# GD32F470IIH6.net
KiCad netlist of a schematic drawn in EasyEDA Pro
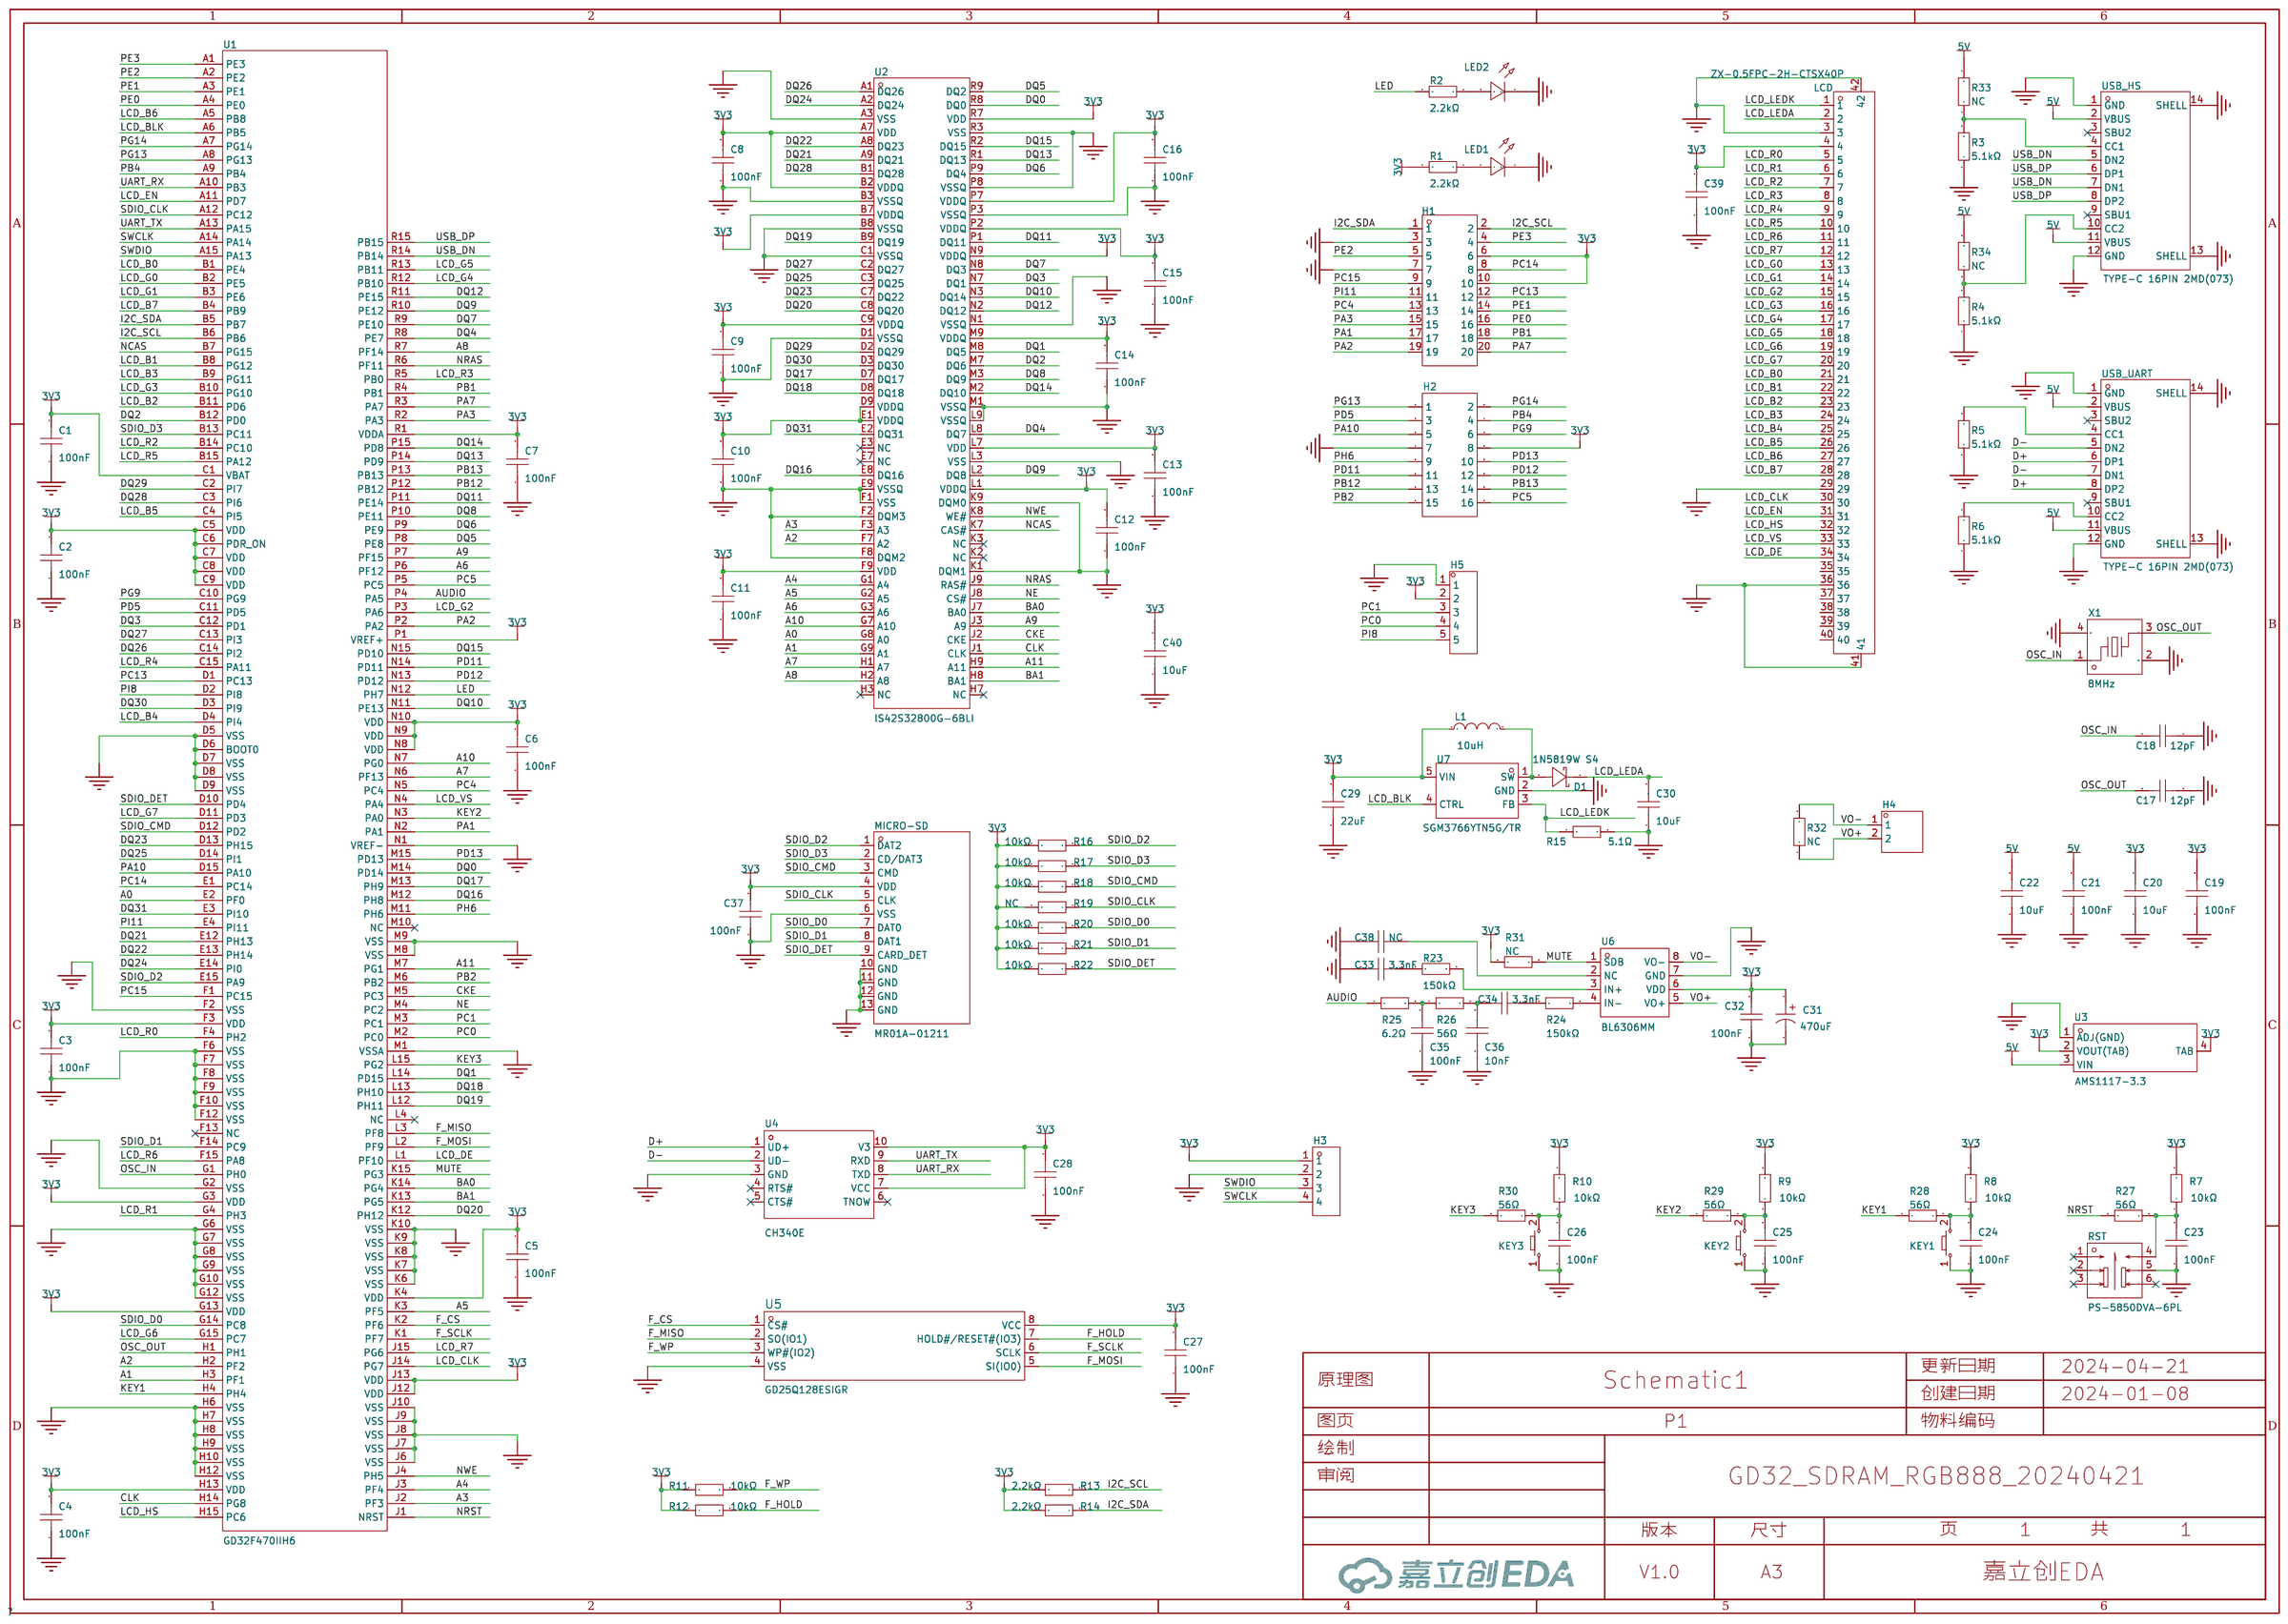
[diagram p0: schematic sheet]

(export (version "E")
  (design (tool "Eeschema 10.0.6"))
  (components
    (comp (ref "C1")
      (value "100nF")
      (footprint "easyedapro:C0402")
      (description "容值:100nF;精度:±10%;额定电压:16V;材质(温度系数):X7R;")
      (fields
        (field (name "Manufacturer Part") "CC0402KRX7R7BB104")
        (field (name "Manufacturer") "YAGEO(国巨)")
      )
      (libsource (lib "easyedapro") (part "CapAcitance"))
    )
    (comp (ref "C2")
      (value "100nF")
      (footprint "easyedapro:C0402")
      (description "容值:100nF;精度:±10%;额定电压:16V;材质(温度系数):X7R;")
      (fields
        (field (name "Manufacturer Part") "CC0402KRX7R7BB104")
        (field (name "Manufacturer") "YAGEO(国巨)")
      )
      (libsource (lib "easyedapro") (part "CapAcitance"))
    )
    (comp (ref "C3")
      (value "100nF")
      (footprint "easyedapro:C0402")
      (description "容值:100nF;精度:±10%;额定电压:16V;材质(温度系数):X7R;")
      (fields
        (field (name "Manufacturer Part") "CC0402KRX7R7BB104")
        (field (name "Manufacturer") "YAGEO(国巨)")
      )
      (libsource (lib "easyedapro") (part "CapAcitance"))
    )
    (comp (ref "C4")
      (value "100nF")
      (footprint "easyedapro:C0402")
      (description "容值:100nF;精度:±10%;额定电压:16V;材质(温度系数):X7R;")
      (fields
        (field (name "Manufacturer Part") "CC0402KRX7R7BB104")
        (field (name "Manufacturer") "YAGEO(国巨)")
      )
      (libsource (lib "easyedapro") (part "CapAcitance"))
    )
    (comp (ref "C5")
      (value "100nF")
      (footprint "easyedapro:C0402")
      (description "容值:100nF;精度:±10%;额定电压:16V;材质(温度系数):X7R;")
      (fields
        (field (name "Manufacturer Part") "CC0402KRX7R7BB104")
        (field (name "Manufacturer") "YAGEO(国巨)")
      )
      (libsource (lib "easyedapro") (part "CapAcitance"))
    )
    (comp (ref "C6")
      (value "100nF")
      (footprint "easyedapro:C0402")
      (description "容值:100nF;精度:±10%;额定电压:16V;材质(温度系数):X7R;")
      (fields
        (field (name "Manufacturer Part") "CC0402KRX7R7BB104")
        (field (name "Manufacturer") "YAGEO(国巨)")
      )
      (libsource (lib "easyedapro") (part "CapAcitance"))
    )
    (comp (ref "C7")
      (value "100nF")
      (footprint "easyedapro:C0402")
      (description "容值:100nF;精度:±10%;额定电压:16V;材质(温度系数):X7R;")
      (fields
        (field (name "Manufacturer Part") "CC0402KRX7R7BB104")
        (field (name "Manufacturer") "YAGEO(国巨)")
      )
      (libsource (lib "easyedapro") (part "CapAcitance"))
    )
    (comp (ref "C8")
      (value "100nF")
      (footprint "easyedapro:C0402")
      (description "容值:100nF;精度:±10%;额定电压:16V;材质(温度系数):X7R;")
      (fields
        (field (name "Manufacturer Part") "CC0402KRX7R7BB104")
        (field (name "Manufacturer") "YAGEO(国巨)")
      )
      (libsource (lib "easyedapro") (part "CapAcitance"))
    )
    (comp (ref "C9")
      (value "100nF")
      (footprint "easyedapro:C0402")
      (description "容值:100nF;精度:±10%;额定电压:16V;材质(温度系数):X7R;")
      (fields
        (field (name "Manufacturer Part") "CC0402KRX7R7BB104")
        (field (name "Manufacturer") "YAGEO(国巨)")
      )
      (libsource (lib "easyedapro") (part "CapAcitance"))
    )
    (comp (ref "C10")
      (value "100nF")
      (footprint "easyedapro:C0402")
      (description "容值:100nF;精度:±10%;额定电压:16V;材质(温度系数):X7R;")
      (fields
        (field (name "Manufacturer Part") "CC0402KRX7R7BB104")
        (field (name "Manufacturer") "YAGEO(国巨)")
      )
      (libsource (lib "easyedapro") (part "CapAcitance"))
    )
    (comp (ref "C11")
      (value "100nF")
      (footprint "easyedapro:C0402")
      (description "容值:100nF;精度:±10%;额定电压:16V;材质(温度系数):X7R;")
      (fields
        (field (name "Manufacturer Part") "CC0402KRX7R7BB104")
        (field (name "Manufacturer") "YAGEO(国巨)")
      )
      (libsource (lib "easyedapro") (part "CapAcitance"))
    )
    (comp (ref "C12")
      (value "100nF")
      (footprint "easyedapro:C0402")
      (description "容值:100nF;精度:±10%;额定电压:16V;材质(温度系数):X7R;")
      (fields
        (field (name "Manufacturer Part") "CC0402KRX7R7BB104")
        (field (name "Manufacturer") "YAGEO(国巨)")
      )
      (libsource (lib "easyedapro") (part "CapAcitance"))
    )
    (comp (ref "C13")
      (value "100nF")
      (footprint "easyedapro:C0402")
      (description "容值:100nF;精度:±10%;额定电压:16V;材质(温度系数):X7R;")
      (fields
        (field (name "Manufacturer Part") "CC0402KRX7R7BB104")
        (field (name "Manufacturer") "YAGEO(国巨)")
      )
      (libsource (lib "easyedapro") (part "CapAcitance"))
    )
    (comp (ref "C14")
      (value "100nF")
      (footprint "easyedapro:C0402")
      (description "容值:100nF;精度:±10%;额定电压:16V;材质(温度系数):X7R;")
      (fields
        (field (name "Manufacturer Part") "CC0402KRX7R7BB104")
        (field (name "Manufacturer") "YAGEO(国巨)")
      )
      (libsource (lib "easyedapro") (part "CapAcitance"))
    )
    (comp (ref "C15")
      (value "100nF")
      (footprint "easyedapro:C0402")
      (description "容值:100nF;精度:±10%;额定电压:16V;材质(温度系数):X7R;")
      (fields
        (field (name "Manufacturer Part") "CC0402KRX7R7BB104")
        (field (name "Manufacturer") "YAGEO(国巨)")
      )
      (libsource (lib "easyedapro") (part "CapAcitance"))
    )
    (comp (ref "C16")
      (value "100nF")
      (footprint "easyedapro:C0402")
      (description "容值:100nF;精度:±10%;额定电压:16V;材质(温度系数):X7R;")
      (fields
        (field (name "Manufacturer Part") "CC0402KRX7R7BB104")
        (field (name "Manufacturer") "YAGEO(国巨)")
      )
      (libsource (lib "easyedapro") (part "CapAcitance"))
    )
    (comp (ref "C17")
      (value "12pF")
      (footprint "easyedapro:C0603")
      (fields
        (field (name "Manufacturer Part") "CL10C120JB8NNNC")
        (field (name "Manufacturer") "SAMSUNG(三星)")
        (field (name "Tolerance") "±5%")
      )
      (libsource (lib "easyedapro") (part "CapAcitance"))
    )
    (comp (ref "C18")
      (value "12pF")
      (footprint "easyedapro:C0603")
      (fields
        (field (name "Manufacturer Part") "CL10C120JB8NNNC")
        (field (name "Manufacturer") "SAMSUNG(三星)")
        (field (name "Tolerance") "±5%")
      )
      (libsource (lib "easyedapro") (part "CapAcitance"))
    )
    (comp (ref "C19")
      (value "100nF")
      (footprint "easyedapro:C0805")
      (description "容值:100nF;精度:±10%;额定电压:50V;材质(温度系数):X7R;")
      (fields (field (name "Manufacturer Part") "0603B104K500NT") (field (name "Manufacturer") "FH(风华)"))
      (libsource (lib "easyedapro") (part "CapAcitance"))
    )
    (comp (ref "C20")
      (value "10uF")
      (footprint "easyedapro:C0805")
      (description "容值:10uF;精度:±10%;额定电压:25V;材质(温度系数):X5R;")
      (fields
        (field (name "Manufacturer Part") "CL21A106KAYNNNE")
        (field (name "Manufacturer") "SAMSUNG(三星)")
      )
      (libsource (lib "easyedapro") (part "CapAcitance"))
    )
    (comp (ref "C21")
      (value "100nF")
      (footprint "easyedapro:C0805")
      (fields
        (field (name "Manufacturer Part") "0603B104K500NT")
        (field (name "Manufacturer") "FH(风华)")
        (field (name "Tolerance") "±10%")
      )
      (libsource (lib "easyedapro") (part "CapAcitance"))
    )
    (comp (ref "C22")
      (value "10uF")
      (footprint "easyedapro:C0805")
      (description "容值:10uF;精度:±10%;额定电压:25V;材质(温度系数):X5R;")
      (fields
        (field (name "Manufacturer Part") "CL21A106KAYNNNE")
        (field (name "Manufacturer") "SAMSUNG(三星)")
      )
      (libsource (lib "easyedapro") (part "CapAcitance"))
    )
    (comp (ref "C23")
      (value "100nF")
      (footprint "easyedapro:C0402")
      (description "容值:100nF;精度:±10%;额定电压:16V;材质(温度系数):X7R;")
      (fields
        (field (name "Manufacturer Part") "CC0402KRX7R7BB104")
        (field (name "Manufacturer") "YAGEO(国巨)")
      )
      (libsource (lib "easyedapro") (part "CapAcitance"))
    )
    (comp (ref "C24")
      (value "100nF")
      (footprint "easyedapro:C0402")
      (description "容值:100nF;精度:±10%;额定电压:16V;材质(温度系数):X7R;")
      (fields
        (field (name "Manufacturer Part") "CC0402KRX7R7BB104")
        (field (name "Manufacturer") "YAGEO(国巨)")
      )
      (libsource (lib "easyedapro") (part "CapAcitance"))
    )
    (comp (ref "C25")
      (value "100nF")
      (footprint "easyedapro:C0402")
      (description "容值:100nF;精度:±10%;额定电压:16V;材质(温度系数):X7R;")
      (fields
        (field (name "Manufacturer Part") "CC0402KRX7R7BB104")
        (field (name "Manufacturer") "YAGEO(国巨)")
      )
      (libsource (lib "easyedapro") (part "CapAcitance"))
    )
    (comp (ref "C26")
      (value "100nF")
      (footprint "easyedapro:C0402")
      (description "容值:100nF;精度:±10%;额定电压:16V;材质(温度系数):X7R;")
      (fields
        (field (name "Manufacturer Part") "CC0402KRX7R7BB104")
        (field (name "Manufacturer") "YAGEO(国巨)")
      )
      (libsource (lib "easyedapro") (part "CapAcitance"))
    )
    (comp (ref "C27")
      (value "100nF")
      (footprint "easyedapro:C0603")
      (fields
        (field (name "Manufacturer Part") "0603B104K500NT")
        (field (name "Manufacturer") "FH(风华)")
        (field (name "Tolerance") "±10%")
      )
      (libsource (lib "easyedapro") (part "CapAcitance"))
    )
    (comp (ref "C28")
      (value "100nF")
      (footprint "easyedapro:C0603")
      (fields
        (field (name "Manufacturer Part") "0603B104K500NT")
        (field (name "Manufacturer") "FH(风华)")
        (field (name "Tolerance") "±10%")
      )
      (libsource (lib "easyedapro") (part "CapAcitance"))
    )
    (comp (ref "C29")
      (value "22uF")
      (footprint "easyedapro:C0603")
      (description "容值:22uF;精度:±20%;额定电压:25V;材质(温度系数):X5R;")
      (fields
        (field (name "Manufacturer Part") "CL21A226MAQNNNE")
        (field (name "Manufacturer") "SAMSUNG(三星)")
      )
      (libsource (lib "easyedapro") (part "CapAcitance"))
    )
    (comp (ref "C30")
      (value "10uF")
      (footprint "easyedapro:C0603")
      (description "容值:10uF;精度:±10%;额定电压:25V;材质(温度系数):X5R;")
      (fields
        (field (name "Manufacturer Part") "CL21A106KAYNNNE")
        (field (name "Manufacturer") "SAMSUNG(三星)")
      )
      (libsource (lib "easyedapro") (part "CapAcitance"))
    )
    (comp (ref "C31")
      (value "470uF")
      (footprint "easyedapro:CAP-TH_BD6.3-P2.50-D0.5-FD")
      (description "容值:470uF;精度:±20%;额定电压:16V;纹波电流:-;等效串联电阻:-;")
      (fields (field (name "Manufacturer Part") "GR1C471M0611") (field (name "Manufacturer") "ROQANG(容强)"))
      (libsource (lib "easyedapro") (part "GR1C471M0611"))
    )
    (comp (ref "C32")
      (value "100nF")
      (footprint "easyedapro:C0603")
      (description "容值:100nF;精度:±10%;额定电压:50V;材质(温度系数):X7R;")
      (fields (field (name "Manufacturer Part") "0603B104K500NT") (field (name "Manufacturer") "FH(风华)"))
      (libsource (lib "easyedapro") (part "CapAcitance"))
    )
    (comp (ref "C33")
      (value "3.3nF")
      (footprint "easyedapro:C0603")
      (fields
        (field (name "Manufacturer Part") "CL10B332KB8NNNC")
        (field (name "Manufacturer") "SAMSUNG(三星)")
        (field (name "Tolerance") "±10%")
      )
      (libsource (lib "easyedapro") (part "CapAcitance"))
    )
    (comp (ref "C34")
      (value "3.3nF")
      (footprint "easyedapro:C0603")
      (fields
        (field (name "Manufacturer Part") "CL10B332KB8NNNC")
        (field (name "Manufacturer") "SAMSUNG(三星)")
        (field (name "Tolerance") "±10%")
      )
      (libsource (lib "easyedapro") (part "CapAcitance"))
    )
    (comp (ref "C35")
      (value "100nF")
      (footprint "easyedapro:C0603")
      (fields
        (field (name "Manufacturer Part") "0603B104K500NT")
        (field (name "Manufacturer") "FH(风华)")
        (field (name "Tolerance") "±10%")
      )
      (libsource (lib "easyedapro") (part "CapAcitance"))
    )
    (comp (ref "C36")
      (value "10nF")
      (footprint "easyedapro:C0603")
      (description "容值:10nF;精度:±10%;额定电压:50V;材质(温度系数):X7R;")
      (fields (field (name "Manufacturer Part") "0603B103K500NT") (field (name "Manufacturer") "FH(风华)"))
      (libsource (lib "easyedapro") (part "CapAcitance"))
    )
    (comp (ref "C37")
      (value "100nF")
      (footprint "easyedapro:C0402")
      (description "容值:100nF;精度:±10%;额定电压:16V;材质(温度系数):X7R;")
      (fields
        (field (name "Manufacturer Part") "CC0402KRX7R7BB104")
        (field (name "Manufacturer") "YAGEO(国巨)")
      )
      (libsource (lib "easyedapro") (part "CapAcitance"))
    )
    (comp (ref "C38")
      (value "NC")
      (footprint "easyedapro:C0603")
      (libsource (lib "easyedapro") (part "CapAcitance"))
    )
    (comp (ref "C39")
      (value "100nF")
      (footprint "easyedapro:C0402")
      (description "容值:100nF;精度:±10%;额定电压:16V;材质(温度系数):X7R;")
      (fields
        (field (name "Manufacturer Part") "CC0402KRX7R7BB104")
        (field (name "Manufacturer") "YAGEO(国巨)")
      )
      (libsource (lib "easyedapro") (part "CapAcitance"))
    )
    (comp (ref "C40")
      (value "10uF")
      (footprint "easyedapro:C0805")
      (description "容值:10uF;精度:±10%;额定电压:25V;材质(温度系数):X5R;")
      (fields
        (field (name "Manufacturer Part") "CL21A106KAYNNNE")
        (field (name "Manufacturer") "SAMSUNG(三星)")
      )
      (libsource (lib "easyedapro") (part "CapAcitance"))
    )
    (comp (ref "D1")
      (value "1N5819W S4")
      (footprint "easyedapro:SOD-123_L2.7-W1.6-LS3.7-FD")
      (description "二极管配置:-;正向压降(Vf):600mV@200mA;直流反向耐压(Vr):40V;平均整流电流(Io):350mA;")
      (fields (field (name "Manufacturer") "KUU"))
      (libsource (lib "easyedapro") (part "1N5819W S4"))
    )
    (comp (ref "H1")
      (value "~")
      (footprint "easyedapro:HDR-TH_20P-P2.54-V-M-R2-C10-S2.54")
      (libsource (lib "easyedapro") (part "HDR-M-2.54_2x10"))
    )
    (comp (ref "H2")
      (value "~")
      (footprint "easyedapro:HDR-TH_16P-P2.54-V-M-R2-C8-S2.54")
      (libsource (lib "easyedapro") (part "HDR-M-2.54_2x8"))
    )
    (comp (ref "H3")
      (value "~")
      (footprint "easyedapro:HDR-TH_4P-P2.54-V-M")
      (libsource (lib "easyedapro") (part "PZ254V-11-04P"))
    )
    (comp (ref "H4")
      (value "~")
      (footprint "easyedapro:HDR-TH_2P-P2.54-V-M-1")
      (libsource (lib "easyedapro") (part "210S-1*2P L=11.6MMGold-plated black"))
    )
    (comp (ref "H5")
      (value "~")
      (footprint "easyedapro:HDR-TH_5P-P2.54-V-M")
      (libsource (lib "easyedapro") (part "MTP125-1105S1"))
    )
    (comp (ref "KEY1")
      (value "K2-1107ST-A4DW-06")
      (footprint "easyedapro:Key_SMD_3x4x2")
      (fields (field (name "Manufacturer") "韩国韩荣"))
      (libsource (lib "easyedapro") (part "轻触按键x2"))
    )
    (comp (ref "KEY2")
      (value "K2-1107ST-A4DW-06")
      (footprint "easyedapro:Key_SMD_3x4x2")
      (fields (field (name "Manufacturer") "韩国韩荣"))
      (libsource (lib "easyedapro") (part "轻触按键x2"))
    )
    (comp (ref "KEY3")
      (value "K2-1107ST-A4DW-06")
      (footprint "easyedapro:Key_SMD_3x4x2")
      (fields (field (name "Manufacturer") "韩国韩荣"))
      (libsource (lib "easyedapro") (part "轻触按键x2"))
    )
    (comp (ref "L1")
      (value "10uH")
      (footprint "easyedapro:IND-SMD_L4.0-W4.0")
      (description "电感值:10uH;精度:±20%;额定电流:2.35A;饱和电流(Isat):3.5A;")
      (fields
        (field (name "Manufacturer Part") "FHD4020S-100MT")
        (field (name "Manufacturer") "cjiang(长江微电)")
      )
      (libsource (lib "easyedapro") (part "FHD4020S-100MT"))
    )
    (comp (ref "LCD")
      (value "ZX-0.5FPC-2H-CTSX40P")
      (footprint "easyedapro:FPC-SMD_40P-P0.50_ZX-0.5FPC-2H-CTSX40P")
      (description "锁定特性:抽屉式;触点类型:上接;触点数量:40P;间距:0.5mm;安装类型:卧贴;工作温度范围:-25°C~+85°C;焊接温度(最大值):260°C;")
      (fields (field (name "Manufacturer") "Megastar(兆星)"))
      (libsource (lib "easyedapro") (part "ZX-0.5FPC-2H-CTSX40P"))
    )
    (comp (ref "LED1")
      (value "XL-2012UGC")
      (footprint "easyedapro:LED_0805")
      (description "发光颜色:翠绿色;功率:80mW;正向电流:25mA;主波长:516nm~525nm;透镜颜色:无色透明透镜;色温:-;发光角度:120°;载带方式:正贴;工作温度:-30℃~+85℃;")
      (fields (field (name "Manufacturer") "XINGLIGHT(成兴光)"))
      (libsource (lib "easyedapro") (part "LED_B"))
    )
    (comp (ref "LED2")
      (value "XL-2012UGC")
      (footprint "easyedapro:LED_0805")
      (description "发光颜色:翠绿色;功率:80mW;正向电流:25mA;主波长:516nm~525nm;透镜颜色:无色透明透镜;色温:-;发光角度:120°;载带方式:正贴;工作温度:-30℃~+85℃;")
      (fields (field (name "Manufacturer") "XINGLIGHT(成兴光)"))
      (libsource (lib "easyedapro") (part "LED_B"))
    )
    (comp (ref "MICRO-SD")
      (value "MR01A-01211")
      (footprint "easyedapro:TF-SMD_MR01A-01211")
      (description "卡类型:MicroSD卡(TF卡);连接器类型:卡座;卡连接方式:自弹式;本体最大高度:1.85mm;工作温度范围:-25°C~+85°C;")
      (fields (field (name "Manufacturer") "ATOM(爱特姆)"))
      (libsource (lib "easyedapro") (part "MR01A-01211"))
    )
    (comp (ref "R1")
      (value "2.2kΩ")
      (footprint "easyedapro:R0603")
      (fields
        (field (name "Manufacturer Part") "0603WAF2201T5E")
        (field (name "Manufacturer") "UNI-ROYAL(厚声)")
        (field (name "Tolerance") "±1%")
      )
      (libsource (lib "easyedapro") (part "电阻"))
    )
    (comp (ref "R2")
      (value "2.2kΩ")
      (footprint "easyedapro:R0603")
      (fields
        (field (name "Manufacturer Part") "0603WAF2201T5E")
        (field (name "Manufacturer") "UNI-ROYAL(厚声)")
        (field (name "Tolerance") "±1%")
      )
      (libsource (lib "easyedapro") (part "电阻"))
    )
    (comp (ref "R3")
      (value "5.1kΩ")
      (footprint "easyedapro:R0603")
      (description "电阻类型:厚膜电阻;阻值:5.1kΩ;精度:±1%;功率:100mW;最大工作电压:75V;温度系数:±100ppm/℃;")
      (fields
        (field (name "Manufacturer Part") "0603WAF5101T5E")
        (field (name "Manufacturer") "UNI-ROYAL(厚声)")
      )
      (libsource (lib "easyedapro") (part "电阻"))
    )
    (comp (ref "R4")
      (value "5.1kΩ")
      (footprint "easyedapro:R0603")
      (description "电阻类型:厚膜电阻;阻值:5.1kΩ;精度:±1%;功率:100mW;最大工作电压:75V;温度系数:±100ppm/℃;")
      (fields
        (field (name "Manufacturer Part") "0603WAF5101T5E")
        (field (name "Manufacturer") "UNI-ROYAL(厚声)")
      )
      (libsource (lib "easyedapro") (part "电阻"))
    )
    (comp (ref "R5")
      (value "5.1kΩ")
      (footprint "easyedapro:R0603")
      (description "电阻类型:厚膜电阻;阻值:5.1kΩ;精度:±1%;功率:100mW;最大工作电压:75V;温度系数:±100ppm/℃;")
      (fields
        (field (name "Manufacturer Part") "0603WAF5101T5E")
        (field (name "Manufacturer") "UNI-ROYAL(厚声)")
      )
      (libsource (lib "easyedapro") (part "电阻"))
    )
    (comp (ref "R6")
      (value "5.1kΩ")
      (footprint "easyedapro:R0603")
      (description "电阻类型:厚膜电阻;阻值:5.1kΩ;精度:±1%;功率:100mW;最大工作电压:75V;温度系数:±100ppm/℃;")
      (fields
        (field (name "Manufacturer Part") "0603WAF5101T5E")
        (field (name "Manufacturer") "UNI-ROYAL(厚声)")
      )
      (libsource (lib "easyedapro") (part "电阻"))
    )
    (comp (ref "R7")
      (value "10kΩ")
      (footprint "easyedapro:R0603")
      (fields
        (field (name "Manufacturer Part") "0603WAF1002T5E")
        (field (name "Manufacturer") "UNI-ROYAL(厚声)")
        (field (name "Tolerance") "±1%")
      )
      (libsource (lib "easyedapro") (part "电阻"))
    )
    (comp (ref "R8")
      (value "10kΩ")
      (footprint "easyedapro:R0603")
      (description "电阻类型:厚膜电阻;阻值:10kΩ;精度:±1%;功率:100mW;最大工作电压:75V;温度系数:±100ppm/℃;")
      (fields
        (field (name "Manufacturer Part") "0603WAF1002T5E")
        (field (name "Manufacturer") "UNI-ROYAL(厚声)")
      )
      (libsource (lib "easyedapro") (part "电阻"))
    )
    (comp (ref "R9")
      (value "10kΩ")
      (footprint "easyedapro:R0603")
      (fields
        (field (name "Manufacturer Part") "0603WAF1002T5E")
        (field (name "Manufacturer") "UNI-ROYAL(厚声)")
        (field (name "Tolerance") "±1%")
      )
      (libsource (lib "easyedapro") (part "电阻"))
    )
    (comp (ref "R10")
      (value "10kΩ")
      (footprint "easyedapro:R0603")
      (fields
        (field (name "Manufacturer Part") "0603WAF1002T5E")
        (field (name "Manufacturer") "UNI-ROYAL(厚声)")
        (field (name "Tolerance") "±1%")
      )
      (libsource (lib "easyedapro") (part "电阻"))
    )
    (comp (ref "R11")
      (value "10kΩ")
      (footprint "easyedapro:R0603")
      (fields
        (field (name "Manufacturer Part") "0603WAF1002T5E")
        (field (name "Manufacturer") "UNI-ROYAL(厚声)")
        (field (name "Tolerance") "±1%")
      )
      (libsource (lib "easyedapro") (part "电阻"))
    )
    (comp (ref "R12")
      (value "10kΩ")
      (footprint "easyedapro:R0603")
      (fields
        (field (name "Manufacturer Part") "0603WAF1002T5E")
        (field (name "Manufacturer") "UNI-ROYAL(厚声)")
        (field (name "Tolerance") "±1%")
      )
      (libsource (lib "easyedapro") (part "电阻"))
    )
    (comp (ref "R13")
      (value "2.2kΩ")
      (footprint "easyedapro:R0603")
      (description "电阻类型:厚膜电阻;阻值:2.2kΩ;精度:±1%;功率:100mW;最大工作电压:75V;温度系数:±100ppm/℃;")
      (fields
        (field (name "Manufacturer Part") "0603WAF2201T5E")
        (field (name "Manufacturer") "UNI-ROYAL(厚声)")
      )
      (libsource (lib "easyedapro") (part "电阻"))
    )
    (comp (ref "R14")
      (value "2.2kΩ")
      (footprint "easyedapro:R0603")
      (description "电阻类型:厚膜电阻;阻值:2.2kΩ;精度:±1%;功率:100mW;最大工作电压:75V;温度系数:±100ppm/℃;")
      (fields
        (field (name "Manufacturer Part") "0603WAF2201T5E")
        (field (name "Manufacturer") "UNI-ROYAL(厚声)")
      )
      (libsource (lib "easyedapro") (part "电阻"))
    )
    (comp (ref "R15")
      (value "5.1Ω")
      (footprint "easyedapro:R0603")
      (description "电阻类型:厚膜电阻;阻值:5.1Ω;精度:±5%;功率:100mW;最大工作电压:75V;温度系数:±400ppm/°C;")
      (fields
        (field (name "Manufacturer Part") "0603WAJ051JT5E")
        (field (name "Manufacturer") "UNI-ROYAL(厚声)")
      )
      (libsource (lib "easyedapro") (part "0603WAJ051JT5E"))
    )
    (comp (ref "R16")
      (value "10kΩ")
      (footprint "easyedapro:R0603")
      (description "电阻类型:厚膜电阻;阻值:10kΩ;精度:±1%;功率:100mW;最大工作电压:75V;温度系数:±100ppm/℃;")
      (fields
        (field (name "Manufacturer Part") "0603WAF1002T5E")
        (field (name "Manufacturer") "UNI-ROYAL(厚声)")
      )
      (libsource (lib "easyedapro") (part "电阻"))
    )
    (comp (ref "R17")
      (value "10kΩ")
      (footprint "easyedapro:R0603")
      (description "电阻类型:厚膜电阻;阻值:10kΩ;精度:±1%;功率:100mW;最大工作电压:75V;温度系数:±100ppm/℃;")
      (fields
        (field (name "Manufacturer Part") "0603WAF1002T5E")
        (field (name "Manufacturer") "UNI-ROYAL(厚声)")
      )
      (libsource (lib "easyedapro") (part "电阻"))
    )
    (comp (ref "R18")
      (value "10kΩ")
      (footprint "easyedapro:R0603")
      (description "电阻类型:厚膜电阻;阻值:10kΩ;精度:±1%;功率:100mW;最大工作电压:75V;温度系数:±100ppm/℃;")
      (fields
        (field (name "Manufacturer Part") "0603WAF1002T5E")
        (field (name "Manufacturer") "UNI-ROYAL(厚声)")
      )
      (libsource (lib "easyedapro") (part "电阻"))
    )
    (comp (ref "R19")
      (value "NC")
      (footprint "easyedapro:R0603")
      (description "电阻类型:厚膜电阻;阻值:10kΩ;精度:±1%;功率:100mW;最大工作电压:75V;温度系数:±100ppm/℃;")
      (fields
        (field (name "Manufacturer Part") "0603WAF1002T5E")
        (field (name "Manufacturer") "UNI-ROYAL(厚声)")
      )
      (libsource (lib "easyedapro") (part "电阻"))
    )
    (comp (ref "R20")
      (value "10kΩ")
      (footprint "easyedapro:R0603")
      (description "电阻类型:厚膜电阻;阻值:10kΩ;精度:±1%;功率:100mW;最大工作电压:75V;温度系数:±100ppm/℃;")
      (fields
        (field (name "Manufacturer Part") "0603WAF1002T5E")
        (field (name "Manufacturer") "UNI-ROYAL(厚声)")
      )
      (libsource (lib "easyedapro") (part "电阻"))
    )
    (comp (ref "R21")
      (value "10kΩ")
      (footprint "easyedapro:R0603")
      (description "电阻类型:厚膜电阻;阻值:10kΩ;精度:±1%;功率:100mW;最大工作电压:75V;温度系数:±100ppm/℃;")
      (fields
        (field (name "Manufacturer Part") "0603WAF1002T5E")
        (field (name "Manufacturer") "UNI-ROYAL(厚声)")
      )
      (libsource (lib "easyedapro") (part "电阻"))
    )
    (comp (ref "R22")
      (value "10kΩ")
      (footprint "easyedapro:R0603")
      (description "电阻类型:厚膜电阻;阻值:10kΩ;精度:±1%;功率:100mW;最大工作电压:75V;温度系数:±100ppm/℃;")
      (fields
        (field (name "Manufacturer Part") "0603WAF1002T5E")
        (field (name "Manufacturer") "UNI-ROYAL(厚声)")
      )
      (libsource (lib "easyedapro") (part "电阻"))
    )
    (comp (ref "R23")
      (value "150kΩ")
      (footprint "easyedapro:R0603")
      (fields
        (field (name "Manufacturer Part") "0603WAF1503T5E")
        (field (name "Manufacturer") "UNI-ROYAL(厚声)")
        (field (name "Tolerance") "±1%")
      )
      (libsource (lib "easyedapro") (part "电阻"))
    )
    (comp (ref "R24")
      (value "150kΩ")
      (footprint "easyedapro:R0603")
      (fields
        (field (name "Manufacturer Part") "0603WAF1503T5E")
        (field (name "Manufacturer") "UNI-ROYAL(厚声)")
        (field (name "Tolerance") "±1%")
      )
      (libsource (lib "easyedapro") (part "电阻"))
    )
    (comp (ref "R25")
      (value "6.2Ω")
      (description "阻值:6.2Ω;精度:±5%;功率:100mW;温度系数:±200ppm/°C;电阻类型:厚膜电阻;")
      (fields
        (field (name "Manufacturer Part") "0603WAJ062JT5E")
        (field (name "Manufacturer") "UNI-ROYAL(厚声)")
      )
      (libsource (lib "easyedapro") (part "0603WAJ062JT5E"))
    )
    (comp (ref "R26")
      (value "56Ω")
      (footprint "easyedapro:R0603")
      (description "电阻类型:厚膜电阻;阻值:56Ω;精度:±1%;功率:100mW;最大工作电压:75V;温度系数:±200ppm/°C;")
      (fields
        (field (name "Manufacturer Part") "0603WAF560JT5E")
        (field (name "Manufacturer") "UNI-ROYAL(厚声)")
      )
      (libsource (lib "easyedapro") (part "0603WAF560JT5E"))
    )
    (comp (ref "R27")
      (value "56Ω")
      (footprint "easyedapro:R0603")
      (description "电阻类型:厚膜电阻;阻值:56Ω;精度:±1%;功率:100mW;最大工作电压:75V;温度系数:±200ppm/°C;")
      (fields
        (field (name "Manufacturer Part") "0603WAF560JT5E")
        (field (name "Manufacturer") "UNI-ROYAL(厚声)")
      )
      (libsource (lib "easyedapro") (part "0603WAF560JT5E"))
    )
    (comp (ref "R28")
      (value "56Ω")
      (footprint "easyedapro:R0603")
      (description "电阻类型:厚膜电阻;阻值:56Ω;精度:±1%;功率:100mW;最大工作电压:75V;温度系数:±200ppm/°C;")
      (fields
        (field (name "Manufacturer Part") "0603WAF560JT5E")
        (field (name "Manufacturer") "UNI-ROYAL(厚声)")
      )
      (libsource (lib "easyedapro") (part "0603WAF560JT5E"))
    )
    (comp (ref "R29")
      (value "56Ω")
      (footprint "easyedapro:R0603")
      (description "电阻类型:厚膜电阻;阻值:56Ω;精度:±1%;功率:100mW;最大工作电压:75V;温度系数:±200ppm/°C;")
      (fields
        (field (name "Manufacturer Part") "0603WAF560JT5E")
        (field (name "Manufacturer") "UNI-ROYAL(厚声)")
      )
      (libsource (lib "easyedapro") (part "0603WAF560JT5E"))
    )
    (comp (ref "R30")
      (value "56Ω")
      (footprint "easyedapro:R0603")
      (description "电阻类型:厚膜电阻;阻值:56Ω;精度:±1%;功率:100mW;最大工作电压:75V;温度系数:±200ppm/°C;")
      (fields
        (field (name "Manufacturer Part") "0603WAF560JT5E")
        (field (name "Manufacturer") "UNI-ROYAL(厚声)")
      )
      (libsource (lib "easyedapro") (part "0603WAF560JT5E"))
    )
    (comp (ref "R31")
      (value "NC")
      (footprint "easyedapro:R0603")
      (fields
        (field (name "Manufacturer Part") "0603WAF1002T5E")
        (field (name "Manufacturer") "UNI-ROYAL(厚声)")
        (field (name "Tolerance") "±1%")
      )
      (libsource (lib "easyedapro") (part "电阻"))
    )
    (comp (ref "R32")
      (value "NC")
      (description "阻值:6.2Ω;精度:±5%;功率:100mW;温度系数:±200ppm/°C;电阻类型:厚膜电阻;")
      (fields
        (field (name "Manufacturer Part") "0603WAJ062JT5E")
        (field (name "Manufacturer") "UNI-ROYAL(厚声)")
      )
      (libsource (lib "easyedapro") (part "0603WAJ062JT5E"))
    )
    (comp (ref "R33")
      (value "NC")
      (footprint "easyedapro:R0603")
      (description "电阻类型:厚膜电阻;阻值:5.1kΩ;精度:±1%;功率:100mW;最大工作电压:75V;温度系数:±100ppm/℃;")
      (fields
        (field (name "Manufacturer Part") "0603WAF5101T5E")
        (field (name "Manufacturer") "UNI-ROYAL(厚声)")
      )
      (libsource (lib "easyedapro") (part "电阻"))
    )
    (comp (ref "R34")
      (value "NC")
      (footprint "easyedapro:R0603")
      (description "电阻类型:厚膜电阻;阻值:5.1kΩ;精度:±1%;功率:100mW;最大工作电压:75V;温度系数:±100ppm/℃;")
      (fields
        (field (name "Manufacturer Part") "0603WAF5101T5E")
        (field (name "Manufacturer") "UNI-ROYAL(厚声)")
      )
      (libsource (lib "easyedapro") (part "电阻"))
    )
    (comp (ref "RST")
      (value "PS-5850DVA-6PL")
      (footprint "easyedapro:SW-TH_6P-L5.8-W5.8-P2.00-LS4.5_PS-5850DVA-6PL")
      (fields (field (name "Manufacturer") "G-Switch(品赞)"))
      (libsource (lib "easyedapro") (part "PS-5850DVA-6PL"))
    )
    (comp (ref "U1")
      (value "GD32F470IIH6")
      (footprint "easyedapro:BGA-201_L10.0-W10.0-P0.65-TL_GD32F450XXX")
      (description "CPU内核:CM4;程序存储容量:512KB;RAM总容量:256KB;GPIO端口数量:140;工作电压范围:2.6V~3.6V;CPU最大主频:200MHz;程序存储器类型:FLASH;")
      (fields (field (name "Manufacturer") "GigaDevice(兆易创新)"))
      (libsource (lib "easyedapro") (part "GD32F450IKH6"))
    )
    (comp (ref "U2")
      (value "IS42S32800G-6BLI")
      (footprint "easyedapro:BGA-90_L13.0-W8.0-R6-C15-P0.80-TL")
      (description "存储器类型:-;存储器容量:-;存储器接口类型:-;工作电压:-;")
      (fields (field (name "Manufacturer") "ISSI(美国芯成)"))
      (libsource (lib "easyedapro") (part "IS42S32800J-7BL"))
    )
    (comp (ref "U3")
      (value "AMS1117-3.3")
      (footprint "easyedapro:SOT-223-4_L6.5-W3.5-P2.30-LS7.0-BR")
      (description "输出类型:固定;最大输入电压:18V;输出电压:3.3V;输出电流:1A;电源纹波抑制比(PSRR):60dB@(120Hz);输出极性:正;")
      (fields (field (name "Manufacturer") "UMW(友台半导体)"))
      (libsource (lib "easyedapro") (part "AMS1117-3.3_C347222"))
    )
    (comp (ref "U4")
      (value "CH340E")
      (footprint "easyedapro:MSOP-10_L3.0-W3.0-P0.50-LS5.0-BL")
      (description "应用功能:收发器;接口协议:USB 2.0;数据速率:2Mbps;")
      (fields (field (name "Manufacturer") "WCH(南京沁恒)"))
      (libsource (lib "easyedapro") (part "CH340E"))
    )
    (comp (ref "U5")
      (value "GD25Q128ESIGR")
      (footprint "easyedapro:SOP-8_L5.3-W5.3-P1.27-LS8.0-BL")
      (description "接口类型:SPI;存储容量:128Mbit;时钟频率(fc):133MHz;")
      (fields (field (name "Manufacturer") "GigaDevice(兆易创新)"))
      (libsource (lib "easyedapro") (part "GD25Q128ESIGR"))
    )
    (comp (ref "U6")
      (value "BL6306MM")
      (footprint "easyedapro:MSOP-8_L3.0-W3.0-P0.65-LS4.9-BL")
      (description "功放类型:-;输出功率:-;")
      (fields (field (name "Manufacturer") "BL(上海贝岭)"))
      (libsource (lib "easyedapro") (part "BL6306M"))
    )
    (comp (ref "U7")
      (value "SGM3766YTN5G/TR")
      (footprint "easyedapro:TSOT-23-5_L2.9-W1.6-P0.95-LS2.8-BL")
      (fields (field (name "Manufacturer") "SGMICRO(圣邦微)"))
      (libsource (lib "easyedapro") (part "SGM3766YTN5G/TR"))
    )
    (comp (ref "USB_HS")
      (value "TYPE-C 16PIN 2MD(073)")
      (footprint "easyedapro:USB-C-SMD_TYPE-C-6PIN-2MD-073")
      (description "连接器类型:Type-C;标准:-;公母:母;端口数量:1;触点数量:16P;安装方式:卧贴;额定电流 - 电源:5A;工作温度范围:-25°C~+85°C;")
      (fields (field (name "Manufacturer") "SHOU HAN(首韩)"))
      (libsource (lib "easyedapro") (part "TYPE-C 16PIN 2MD(073)"))
    )
    (comp (ref "USB_UART")
      (value "TYPE-C 16PIN 2MD(073)")
      (footprint "easyedapro:USB-C-SMD_TYPE-C-6PIN-2MD-073")
      (description "连接器类型:Type-C;标准:-;公母:母;端口数量:1;触点数量:16P;安装方式:卧贴;额定电流 - 电源:5A;工作温度范围:-25°C~+85°C;")
      (fields (field (name "Manufacturer") "SHOU HAN(首韩)"))
      (libsource (lib "easyedapro") (part "TYPE-C 16PIN 2MD(073)"))
    )
    (comp (ref "X1")
      (value "8MHz")
      (footprint "easyedapro:OSC-SMD_4P-L3.2-W2.5-BL")
      (description "晶振类型:贴片晶振;频率:8MHz;常温频差:±10ppm;外接负载电容:12pF;频率稳定度(全温):±30ppm;")
      (fields (field (name "Manufacturer Part") "X32258MOB4SI") (field (name "Manufacturer") "YXC(扬兴晶振)"))
      (libsource (lib "easyedapro") (part "X32258MOB4SI"))
    )
  )
  (nets
    (net (code "1") (name "/A0") (class "Default")
      (node (ref "U1") (pin "E2") (pinfunction "PF0_E2") (pintype "unspecified"))
      (node (ref "U2") (pin "G8") (pinfunction "A0_G8") (pintype "input"))
    )
    (net (code "2") (name "/A1") (class "Default")
      (node (ref "U1") (pin "H3") (pinfunction "PF1_H3") (pintype "unspecified"))
      (node (ref "U2") (pin "G9") (pinfunction "A1_G9") (pintype "input"))
    )
    (net (code "3") (name "/A2") (class "Default")
      (node (ref "U1") (pin "H2") (pinfunction "PF2_H2") (pintype "unspecified"))
      (node (ref "U2") (pin "F7") (pinfunction "A2_F7") (pintype "input"))
    )
    (net (code "4") (name "/A3") (class "Default")
      (node (ref "U1") (pin "J2") (pinfunction "PF3_J2") (pintype "unspecified"))
      (node (ref "U2") (pin "F3") (pinfunction "A3_F3") (pintype "input"))
    )
    (net (code "5") (name "/A4") (class "Default")
      (node (ref "U1") (pin "J3") (pinfunction "PF4_J3") (pintype "unspecified"))
      (node (ref "U2") (pin "G1") (pinfunction "A4_G1") (pintype "input"))
    )
    (net (code "6") (name "/A5") (class "Default")
      (node (ref "U1") (pin "K3") (pinfunction "PF5_K3") (pintype "unspecified"))
      (node (ref "U2") (pin "G2") (pinfunction "A5_G2") (pintype "input"))
    )
    (net (code "7") (name "/A6") (class "Default")
      (node (ref "U1") (pin "P6") (pinfunction "PF12_P6") (pintype "unspecified"))
      (node (ref "U2") (pin "G3") (pinfunction "A6_G3") (pintype "input"))
    )
    (net (code "8") (name "/A7") (class "Default")
      (node (ref "U1") (pin "N6") (pinfunction "PF13_N6") (pintype "unspecified"))
      (node (ref "U2") (pin "H1") (pinfunction "A7_H1") (pintype "input"))
    )
    (net (code "9") (name "/A8") (class "Default")
      (node (ref "U1") (pin "R7") (pinfunction "PF14_R7") (pintype "unspecified"))
      (node (ref "U2") (pin "H2") (pinfunction "A8_H2") (pintype "input"))
    )
    (net (code "10") (name "/A9") (class "Default")
      (node (ref "U1") (pin "P7") (pinfunction "PF15_P7") (pintype "unspecified"))
      (node (ref "U2") (pin "J3") (pinfunction "A9_J3") (pintype "input"))
    )
    (net (code "11") (name "/A10") (class "Default")
      (node (ref "U1") (pin "N7") (pinfunction "PG0_N7") (pintype "unspecified"))
      (node (ref "U2") (pin "G7") (pinfunction "A10_G7") (pintype "input"))
    )
    (net (code "12") (name "/A11") (class "Default")
      (node (ref "U1") (pin "M7") (pinfunction "PG1_M7") (pintype "unspecified"))
      (node (ref "U2") (pin "H9") (pinfunction "A11_H9") (pintype "input"))
    )
    (net (code "13") (name "/AUDIO") (class "Default")
      (node (ref "R25") (pin "1") (pinfunction "1_1") (pintype "input"))
      (node (ref "U1") (pin "P4") (pinfunction "PA5_P4") (pintype "unspecified"))
    )
    (net (code "14") (name "/BA0") (class "Default")
      (node (ref "U1") (pin "K14") (pinfunction "PG4_K14") (pintype "unspecified"))
      (node (ref "U2") (pin "J7") (pinfunction "BA0_J7") (pintype "input"))
    )
    (net (code "15") (name "/BA1") (class "Default")
      (node (ref "U1") (pin "K13") (pinfunction "PG5_K13") (pintype "unspecified"))
      (node (ref "U2") (pin "H8") (pinfunction "BA1_H8") (pintype "input"))
    )
    (net (code "16") (name "/CKE") (class "Default")
      (node (ref "U1") (pin "M5") (pinfunction "PC3_M5") (pintype "unspecified"))
      (node (ref "U2") (pin "J2") (pinfunction "CKE_J2") (pintype "input"))
    )
    (net (code "17") (name "/CLK") (class "Default")
      (node (ref "U1") (pin "H14") (pinfunction "PG8_H14") (pintype "unspecified"))
      (node (ref "U2") (pin "J1") (pinfunction "CLK_J1") (pintype "input"))
    )
    (net (code "18") (name "/D+") (class "Default")
      (node (ref "U4") (pin "1") (pinfunction "UD+_1") (pintype "unspecified"))
      (node (ref "USB_UART") (pin "6") (pinfunction "DP1_6") (pintype "unspecified"))
      (node (ref "USB_UART") (pin "8") (pinfunction "DP2_8") (pintype "unspecified"))
    )
    (net (code "19") (name "/D-") (class "Default")
      (node (ref "U4") (pin "2") (pinfunction "UD-_2") (pintype "unspecified"))
      (node (ref "USB_UART") (pin "5") (pinfunction "DN2_5") (pintype "unspecified"))
      (node (ref "USB_UART") (pin "7") (pinfunction "DN1_7") (pintype "unspecified"))
    )
    (net (code "20") (name "/DQ0") (class "Default")
      (node (ref "U1") (pin "M14") (pinfunction "PD14_M14") (pintype "unspecified"))
      (node (ref "U2") (pin "R8") (pinfunction "DQ0_R8") (pintype "input"))
    )
    (net (code "21") (name "/DQ1") (class "Default")
      (node (ref "U1") (pin "L14") (pinfunction "PD15_L14") (pintype "unspecified"))
      (node (ref "U2") (pin "M8") (pinfunction "DQ5_M8") (pintype "input"))
    )
    (net (code "22") (name "/DQ2") (class "Default")
      (node (ref "U1") (pin "B12") (pinfunction "PD0_B12") (pintype "unspecified"))
      (node (ref "U2") (pin "M7") (pinfunction "DQ6_M7") (pintype "input"))
    )
    (net (code "23") (name "/DQ3") (class "Default")
      (node (ref "U1") (pin "C12") (pinfunction "PD1_C12") (pintype "unspecified"))
      (node (ref "U2") (pin "N7") (pinfunction "DQ1_N7") (pintype "input"))
    )
    (net (code "24") (name "/DQ4") (class "Default")
      (node (ref "U1") (pin "R8") (pinfunction "PE7_R8") (pintype "unspecified"))
      (node (ref "U2") (pin "L8") (pinfunction "DQ7_L8") (pintype "input"))
    )
    (net (code "25") (name "/DQ5") (class "Default")
      (node (ref "U1") (pin "P8") (pinfunction "PE8_P8") (pintype "unspecified"))
      (node (ref "U2") (pin "R9") (pinfunction "DQ2_R9") (pintype "input"))
    )
    (net (code "26") (name "/DQ6") (class "Default")
      (node (ref "U1") (pin "P9") (pinfunction "PE9_P9") (pintype "unspecified"))
      (node (ref "U2") (pin "P9") (pinfunction "DQ4_P9") (pintype "input"))
    )
    (net (code "27") (name "/DQ7") (class "Default")
      (node (ref "U1") (pin "R9") (pinfunction "PE10_R9") (pintype "unspecified"))
      (node (ref "U2") (pin "N8") (pinfunction "DQ3_N8") (pintype "input"))
    )
    (net (code "28") (name "/DQ8") (class "Default")
      (node (ref "U1") (pin "P10") (pinfunction "PE11_P10") (pintype "unspecified"))
      (node (ref "U2") (pin "M3") (pinfunction "DQ9_M3") (pintype "input"))
    )
    (net (code "29") (name "/DQ9") (class "Default")
      (node (ref "U1") (pin "R10") (pinfunction "PE12_R10") (pintype "unspecified"))
      (node (ref "U2") (pin "L2") (pinfunction "DQ8_L2") (pintype "input"))
    )
    (net (code "30") (name "/DQ10") (class "Default")
      (node (ref "U1") (pin "N11") (pinfunction "PE13_N11") (pintype "unspecified"))
      (node (ref "U2") (pin "N3") (pinfunction "DQ14_N3") (pintype "input"))
    )
    (net (code "31") (name "/DQ11") (class "Default")
      (node (ref "U1") (pin "P11") (pinfunction "PE14_P11") (pintype "unspecified"))
      (node (ref "U2") (pin "P1") (pinfunction "DQ11_P1") (pintype "input"))
    )
    (net (code "32") (name "/DQ12") (class "Default")
      (node (ref "U1") (pin "R11") (pinfunction "PE15_R11") (pintype "unspecified"))
      (node (ref "U2") (pin "N2") (pinfunction "DQ12_N2") (pintype "input"))
    )
    (net (code "33") (name "/DQ13") (class "Default")
      (node (ref "U1") (pin "P14") (pinfunction "PD9_P14") (pintype "unspecified"))
      (node (ref "U2") (pin "R1") (pinfunction "DQ13_R1") (pintype "input"))
    )
    (net (code "34") (name "/DQ14") (class "Default")
      (node (ref "U1") (pin "P15") (pinfunction "PD8_P15") (pintype "unspecified"))
      (node (ref "U2") (pin "M2") (pinfunction "DQ10_M2") (pintype "input"))
    )
    (net (code "35") (name "/DQ15") (class "Default")
      (node (ref "U1") (pin "N15") (pinfunction "PD10_N15") (pintype "unspecified"))
      (node (ref "U2") (pin "R2") (pinfunction "DQ15_R2") (pintype "input"))
    )
    (net (code "36") (name "/DQ16") (class "Default")
      (node (ref "U1") (pin "M12") (pinfunction "PH8_M12") (pintype "unspecified"))
      (node (ref "U2") (pin "E8") (pinfunction "DQ16_E8") (pintype "input"))
    )
    (net (code "37") (name "/DQ17") (class "Default")
      (node (ref "U1") (pin "M13") (pinfunction "PH9_M13") (pintype "unspecified"))
      (node (ref "U2") (pin "D7") (pinfunction "DQ17_D7") (pintype "input"))
    )
    (net (code "38") (name "/DQ18") (class "Default")
      (node (ref "U1") (pin "L13") (pinfunction "PH10_L13") (pintype "unspecified"))
      (node (ref "U2") (pin "D8") (pinfunction "DQ18_D8") (pintype "input"))
    )
    (net (code "39") (name "/DQ19") (class "Default")
      (node (ref "U1") (pin "L12") (pinfunction "PH11_L12") (pintype "unspecified"))
      (node (ref "U2") (pin "B9") (pinfunction "DQ19_B9") (pintype "input"))
    )
    (net (code "40") (name "/DQ20") (class "Default")
      (node (ref "U1") (pin "K12") (pinfunction "PH12_K12") (pintype "unspecified"))
      (node (ref "U2") (pin "C8") (pinfunction "DQ20_C8") (pintype "input"))
    )
    (net (code "41") (name "/DQ21") (class "Default")
      (node (ref "U1") (pin "E12") (pinfunction "PH13_E12") (pintype "unspecified"))
      (node (ref "U2") (pin "A9") (pinfunction "DQ21_A9") (pintype "input"))
    )
    (net (code "42") (name "/DQ22") (class "Default")
      (node (ref "U1") (pin "E13") (pinfunction "PH14_E13") (pintype "unspecified"))
      (node (ref "U2") (pin "A8") (pinfunction "DQ23_A8") (pintype "input"))
    )
    (net (code "43") (name "/DQ23") (class "Default")
      (node (ref "U1") (pin "D13") (pinfunction "PH15_D13") (pintype "unspecified"))
      (node (ref "U2") (pin "C7") (pinfunction "DQ22_C7") (pintype "input"))
    )
    (net (code "44") (name "/DQ24") (class "Default")
      (node (ref "U1") (pin "E14") (pinfunction "PI0_E14") (pintype "unspecified"))
      (node (ref "U2") (pin "A2") (pinfunction "DQ24_A2") (pintype "input"))
    )
    (net (code "45") (name "/DQ25") (class "Default")
      (node (ref "U1") (pin "D14") (pinfunction "PI1_D14") (pintype "unspecified"))
      (node (ref "U2") (pin "C3") (pinfunction "DQ25_C3") (pintype "input"))
    )
    (net (code "46") (name "/DQ26") (class "Default")
      (node (ref "U1") (pin "C14") (pinfunction "PI2_C14") (pintype "unspecified"))
      (node (ref "U2") (pin "A1") (pinfunction "DQ26_A1") (pintype "input"))
    )
    (net (code "47") (name "/DQ27") (class "Default")
      (node (ref "U1") (pin "C13") (pinfunction "PI3_C13") (pintype "unspecified"))
      (node (ref "U2") (pin "C2") (pinfunction "DQ27_C2") (pintype "input"))
    )
    (net (code "48") (name "/DQ28") (class "Default")
      (node (ref "U1") (pin "C3") (pinfunction "PI6_C3") (pintype "unspecified"))
      (node (ref "U2") (pin "B1") (pinfunction "DQ28_B1") (pintype "input"))
    )
    (net (code "49") (name "/DQ29") (class "Default")
      (node (ref "U1") (pin "C2") (pinfunction "PI7_C2") (pintype "unspecified"))
      (node (ref "U2") (pin "D2") (pinfunction "DQ29_D2") (pintype "input"))
    )
    (net (code "50") (name "/DQ30") (class "Default")
      (node (ref "U1") (pin "D3") (pinfunction "PI9_D3") (pintype "unspecified"))
      (node (ref "U2") (pin "D3") (pinfunction "DQ30_D3") (pintype "input"))
    )
    (net (code "51") (name "/DQ31") (class "Default")
      (node (ref "U1") (pin "E3") (pinfunction "PI10_E3") (pintype "unspecified"))
      (node (ref "U2") (pin "E2") (pinfunction "DQ31_E2") (pintype "input"))
    )
    (net (code "52") (name "/F_CS") (class "Default")
      (node (ref "U1") (pin "K2") (pinfunction "PF6_K2") (pintype "unspecified"))
      (node (ref "U5") (pin "1") (pinfunction "CS#_1") (pintype "input"))
    )
    (net (code "53") (name "/F_HOLD") (class "Default")
      (node (ref "R12") (pin "2") (pinfunction "2_2") (pintype "input"))
      (node (ref "U5") (pin "7") (pinfunction "HOLD#/RESET#(IO3)_7") (pintype "input"))
    )
    (net (code "54") (name "/F_MISO") (class "Default")
      (node (ref "U1") (pin "L3") (pinfunction "PF8_L3") (pintype "unspecified"))
      (node (ref "U5") (pin "2") (pinfunction "SO(IO1)_2") (pintype "input"))
    )
    (net (code "55") (name "/F_MOSI") (class "Default")
      (node (ref "U1") (pin "L2") (pinfunction "PF9_L2") (pintype "unspecified"))
      (node (ref "U5") (pin "5") (pinfunction "SI(IO0)_5") (pintype "input"))
    )
    (net (code "56") (name "/F_SCLK") (class "Default")
      (node (ref "U1") (pin "K1") (pinfunction "PF7_K1") (pintype "unspecified"))
      (node (ref "U5") (pin "6") (pinfunction "SCLK_6") (pintype "input"))
    )
    (net (code "57") (name "/F_WP") (class "Default")
      (node (ref "R11") (pin "2") (pinfunction "2_2") (pintype "input"))
      (node (ref "U5") (pin "3") (pinfunction "WP#(IO2)_3") (pintype "input"))
    )
    (net (code "58") (name "/I2C_SCL") (class "Default")
      (node (ref "H1") (pin "2") (pinfunction "2_2") (pintype "input"))
      (node (ref "R13") (pin "1") (pinfunction "1_1") (pintype "input"))
      (node (ref "U1") (pin "B6") (pinfunction "PB6_B6") (pintype "unspecified"))
    )
    (net (code "59") (name "/I2C_SDA") (class "Default")
      (node (ref "H1") (pin "1") (pinfunction "1_1") (pintype "input"))
      (node (ref "R14") (pin "1") (pinfunction "1_1") (pintype "input"))
      (node (ref "U1") (pin "B5") (pinfunction "PB7_B5") (pintype "unspecified"))
    )
    (net (code "60") (name "/KEY1") (class "Default")
      (node (ref "R28") (pin "1") (pinfunction "1_1") (pintype "input"))
      (node (ref "U1") (pin "H4") (pinfunction "PH4_H4") (pintype "unspecified"))
    )
    (net (code "61") (name "/KEY2") (class "Default")
      (node (ref "R29") (pin "1") (pinfunction "1_1") (pintype "input"))
      (node (ref "U1") (pin "N3") (pinfunction "PA0_N3") (pintype "unspecified"))
    )
    (net (code "62") (name "/KEY3") (class "Default")
      (node (ref "R30") (pin "1") (pinfunction "1_1") (pintype "input"))
      (node (ref "U1") (pin "L15") (pinfunction "PG2_L15") (pintype "unspecified"))
    )
    (net (code "63") (name "/LCD_B0") (class "Default")
      (node (ref "LCD") (pin "21") (pinfunction "21_21") (pintype "unspecified"))
      (node (ref "U1") (pin "B1") (pinfunction "PE4_B1") (pintype "unspecified"))
    )
    (net (code "64") (name "/LCD_B1") (class "Default")
      (node (ref "LCD") (pin "22") (pinfunction "22_22") (pintype "unspecified"))
      (node (ref "U1") (pin "B8") (pinfunction "PG12_B8") (pintype "unspecified"))
    )
    (net (code "65") (name "/LCD_B2") (class "Default")
      (node (ref "LCD") (pin "23") (pinfunction "23_23") (pintype "unspecified"))
      (node (ref "U1") (pin "B11") (pinfunction "PD6_B11") (pintype "unspecified"))
    )
    (net (code "66") (name "/LCD_B3") (class "Default")
      (node (ref "LCD") (pin "24") (pinfunction "24_24") (pintype "unspecified"))
      (node (ref "U1") (pin "B9") (pinfunction "PG11_B9") (pintype "unspecified"))
    )
    (net (code "67") (name "/LCD_B4") (class "Default")
      (node (ref "LCD") (pin "25") (pinfunction "25_25") (pintype "unspecified"))
      (node (ref "U1") (pin "D4") (pinfunction "PI4_D4") (pintype "unspecified"))
    )
    (net (code "68") (name "/LCD_B5") (class "Default")
      (node (ref "LCD") (pin "26") (pinfunction "26_26") (pintype "unspecified"))
      (node (ref "U1") (pin "C4") (pinfunction "PI5_C4") (pintype "unspecified"))
    )
    (net (code "69") (name "/LCD_B6") (class "Default")
      (node (ref "LCD") (pin "27") (pinfunction "27_27") (pintype "unspecified"))
      (node (ref "U1") (pin "A5") (pinfunction "PB8_A5") (pintype "unspecified"))
    )
    (net (code "70") (name "/LCD_B7") (class "Default")
      (node (ref "LCD") (pin "28") (pinfunction "28_28") (pintype "unspecified"))
      (node (ref "U1") (pin "B4") (pinfunction "PB9_B4") (pintype "unspecified"))
    )
    (net (code "71") (name "/LCD_BLK") (class "Default")
      (node (ref "U1") (pin "A6") (pinfunction "PB5_A6") (pintype "unspecified"))
      (node (ref "U7") (pin "4") (pinfunction "CTRL_4") (pintype "unspecified"))
    )
    (net (code "72") (name "/LCD_CLK") (class "Default")
      (node (ref "LCD") (pin "30") (pinfunction "30_30") (pintype "unspecified"))
      (node (ref "U1") (pin "J14") (pinfunction "PG7_J14") (pintype "unspecified"))
    )
    (net (code "73") (name "/LCD_DE") (class "Default")
      (node (ref "LCD") (pin "34") (pinfunction "34_34") (pintype "unspecified"))
      (node (ref "U1") (pin "L1") (pinfunction "PF10_L1") (pintype "unspecified"))
    )
    (net (code "74") (name "/LCD_EN") (class "Default")
      (node (ref "LCD") (pin "31") (pinfunction "31_31") (pintype "unspecified"))
      (node (ref "U1") (pin "A11") (pinfunction "PD7_A11") (pintype "unspecified"))
    )
    (net (code "75") (name "/LCD_G0") (class "Default")
      (node (ref "LCD") (pin "13") (pinfunction "13_13") (pintype "unspecified"))
      (node (ref "U1") (pin "B2") (pinfunction "PE5_B2") (pintype "unspecified"))
    )
    (net (code "76") (name "/LCD_G1") (class "Default")
      (node (ref "LCD") (pin "14") (pinfunction "14_14") (pintype "unspecified"))
      (node (ref "U1") (pin "B3") (pinfunction "PE6_B3") (pintype "unspecified"))
    )
    (net (code "77") (name "/LCD_G2") (class "Default")
      (node (ref "LCD") (pin "15") (pinfunction "15_15") (pintype "unspecified"))
      (node (ref "U1") (pin "P3") (pinfunction "PA6_P3") (pintype "unspecified"))
    )
    (net (code "78") (name "/LCD_G3") (class "Default")
      (node (ref "LCD") (pin "16") (pinfunction "16_16") (pintype "unspecified"))
      (node (ref "U1") (pin "B10") (pinfunction "PG10_B10") (pintype "unspecified"))
    )
    (net (code "79") (name "/LCD_G4") (class "Default")
      (node (ref "LCD") (pin "17") (pinfunction "17_17") (pintype "unspecified"))
      (node (ref "U1") (pin "R12") (pinfunction "PB10_R12") (pintype "unspecified"))
    )
    (net (code "80") (name "/LCD_G5") (class "Default")
      (node (ref "LCD") (pin "18") (pinfunction "18_18") (pintype "unspecified"))
      (node (ref "U1") (pin "R13") (pinfunction "PB11_R13") (pintype "unspecified"))
    )
    (net (code "81") (name "/LCD_G6") (class "Default")
      (node (ref "LCD") (pin "19") (pinfunction "19_19") (pintype "unspecified"))
      (node (ref "U1") (pin "G15") (pinfunction "PC7_G15") (pintype "unspecified"))
    )
    (net (code "82") (name "/LCD_G7") (class "Default")
      (node (ref "LCD") (pin "20") (pinfunction "20_20") (pintype "unspecified"))
      (node (ref "U1") (pin "D11") (pinfunction "PD3_D11") (pintype "unspecified"))
    )
    (net (code "83") (name "/LCD_HS") (class "Default")
      (node (ref "LCD") (pin "32") (pinfunction "32_32") (pintype "unspecified"))
      (node (ref "U1") (pin "H15") (pinfunction "PC6_H15") (pintype "unspecified"))
    )
    (net (code "84") (name "/LCD_LEDA") (class "Default")
      (node (ref "C30") (pin "2") (pinfunction "2_2") (pintype "input"))
      (node (ref "D1") (pin "2") (pinfunction "K_2") (pintype "unspecified"))
      (node (ref "LCD") (pin "2") (pinfunction "2_2") (pintype "unspecified"))
    )
    (net (code "85") (name "/LCD_LEDK") (class "Default")
      (node (ref "LCD") (pin "1") (pinfunction "1_1") (pintype "unspecified"))
      (node (ref "R15") (pin "1") (pinfunction "1_1") (pintype "input"))
      (node (ref "U7") (pin "3") (pinfunction "FB_3") (pintype "unspecified"))
    )
    (net (code "86") (name "/LCD_R0") (class "Default")
      (node (ref "LCD") (pin "5") (pinfunction "5_5") (pintype "unspecified"))
      (node (ref "U1") (pin "F4") (pinfunction "PH2_F4") (pintype "unspecified"))
    )
    (net (code "87") (name "/LCD_R1") (class "Default")
      (node (ref "LCD") (pin "6") (pinfunction "6_6") (pintype "unspecified"))
      (node (ref "U1") (pin "G4") (pinfunction "PH3_G4") (pintype "unspecified"))
    )
    (net (code "88") (name "/LCD_R2") (class "Default")
      (node (ref "LCD") (pin "7") (pinfunction "7_7") (pintype "unspecified"))
      (node (ref "U1") (pin "B14") (pinfunction "PC10_B14") (pintype "unspecified"))
    )
    (net (code "89") (name "/LCD_R3") (class "Default")
      (node (ref "LCD") (pin "8") (pinfunction "8_8") (pintype "unspecified"))
      (node (ref "U1") (pin "R5") (pinfunction "PB0_R5") (pintype "unspecified"))
    )
    (net (code "90") (name "/LCD_R4") (class "Default")
      (node (ref "LCD") (pin "9") (pinfunction "9_9") (pintype "unspecified"))
      (node (ref "U1") (pin "C15") (pinfunction "PA11_C15") (pintype "unspecified"))
    )
    (net (code "91") (name "/LCD_R5") (class "Default")
      (node (ref "LCD") (pin "10") (pinfunction "10_10") (pintype "unspecified"))
      (node (ref "U1") (pin "B15") (pinfunction "PA12_B15") (pintype "unspecified"))
    )
    (net (code "92") (name "/LCD_R6") (class "Default")
      (node (ref "LCD") (pin "11") (pinfunction "11_11") (pintype "unspecified"))
      (node (ref "U1") (pin "F15") (pinfunction "PA8_F15") (pintype "unspecified"))
    )
    (net (code "93") (name "/LCD_R7") (class "Default")
      (node (ref "LCD") (pin "12") (pinfunction "12_12") (pintype "unspecified"))
      (node (ref "U1") (pin "J15") (pinfunction "PG6_J15") (pintype "unspecified"))
    )
    (net (code "94") (name "/LCD_VS") (class "Default")
      (node (ref "LCD") (pin "33") (pinfunction "33_33") (pintype "unspecified"))
      (node (ref "U1") (pin "N4") (pinfunction "PA4_N4") (pintype "unspecified"))
    )
    (net (code "95") (name "/LED") (class "Default")
      (node (ref "R2") (pin "2") (pinfunction "2_2") (pintype "input"))
      (node (ref "U1") (pin "N12") (pinfunction "PH7_N12") (pintype "unspecified"))
    )
    (net (code "96") (name "/MUTE") (class "Default")
      (node (ref "R31") (pin "2") (pinfunction "2_2") (pintype "input"))
      (node (ref "U1") (pin "K15") (pinfunction "PG3_K15") (pintype "unspecified"))
      (node (ref "U6") (pin "1") (pinfunction "SDB_1") (pintype "unspecified"))
    )
    (net (code "97") (name "/NCAS") (class "Default")
      (node (ref "U1") (pin "B7") (pinfunction "PG15_B7") (pintype "unspecified"))
      (node (ref "U2") (pin "K7") (pinfunction "CAS#_K7") (pintype "input"))
    )
    (net (code "98") (name "/NE") (class "Default")
      (node (ref "U1") (pin "M4") (pinfunction "PC2_M4") (pintype "unspecified"))
      (node (ref "U2") (pin "J8") (pinfunction "CS#_J8") (pintype "input"))
    )
    (net (code "99") (name "/NRAS") (class "Default")
      (node (ref "U1") (pin "R6") (pinfunction "PF11_R6") (pintype "unspecified"))
      (node (ref "U2") (pin "J9") (pinfunction "RAS#_J9") (pintype "input"))
    )
    (net (code "100") (name "/NRST") (class "Default")
      (node (ref "R27") (pin "1") (pinfunction "1_1") (pintype "input"))
      (node (ref "U1") (pin "J1") (pinfunction "NRST_J1") (pintype "unspecified"))
    )
    (net (code "101") (name "/NWE") (class "Default")
      (node (ref "U1") (pin "J4") (pinfunction "PH5_J4") (pintype "unspecified"))
      (node (ref "U2") (pin "K8") (pinfunction "WE#_K8") (pintype "input"))
    )
    (net (code "102") (name "/OSC_IN") (class "Default")
      (node (ref "C18") (pin "1") (pinfunction "1_1") (pintype "input"))
      (node (ref "U1") (pin "G1") (pinfunction "PH0_G1") (pintype "unspecified"))
      (node (ref "X1") (pin "1") (pinfunction "1_1") (pintype "input"))
    )
    (net (code "103") (name "/OSC_OUT") (class "Default")
      (node (ref "C17") (pin "1") (pinfunction "1_1") (pintype "input"))
      (node (ref "U1") (pin "H1") (pinfunction "PH1_H1") (pintype "unspecified"))
      (node (ref "X1") (pin "3") (pinfunction "3_3") (pintype "input"))
    )
    (net (code "104") (name "/PA1") (class "Default")
      (node (ref "H1") (pin "17") (pinfunction "17_17") (pintype "input"))
      (node (ref "U1") (pin "N2") (pinfunction "PA1_N2") (pintype "unspecified"))
    )
    (net (code "105") (name "/PA2") (class "Default")
      (node (ref "H1") (pin "19") (pinfunction "19_19") (pintype "input"))
      (node (ref "U1") (pin "P2") (pinfunction "PA2_P2") (pintype "unspecified"))
    )
    (net (code "106") (name "/PA3") (class "Default")
      (node (ref "H1") (pin "15") (pinfunction "15_15") (pintype "input"))
      (node (ref "U1") (pin "R2") (pinfunction "PA3_R2") (pintype "unspecified"))
    )
    (net (code "107") (name "/PA7") (class "Default")
      (node (ref "H1") (pin "20") (pinfunction "20_20") (pintype "input"))
      (node (ref "U1") (pin "R3") (pinfunction "PA7_R3") (pintype "unspecified"))
    )
    (net (code "108") (name "/PA10") (class "Default")
      (node (ref "H2") (pin "5") (pinfunction "5_5") (pintype "input"))
      (node (ref "U1") (pin "D15") (pinfunction "PA10_D15") (pintype "unspecified"))
    )
    (net (code "109") (name "/PB1") (class "Default")
      (node (ref "H1") (pin "18") (pinfunction "18_18") (pintype "input"))
      (node (ref "U1") (pin "R4") (pinfunction "PB1_R4") (pintype "unspecified"))
    )
    (net (code "110") (name "/PB2") (class "Default")
      (node (ref "H2") (pin "15") (pinfunction "15_15") (pintype "input"))
      (node (ref "U1") (pin "M6") (pinfunction "PB2_M6") (pintype "unspecified"))
    )
    (net (code "111") (name "/PB4") (class "Default")
      (node (ref "H2") (pin "4") (pinfunction "4_4") (pintype "input"))
      (node (ref "U1") (pin "A9") (pinfunction "PB4_A9") (pintype "unspecified"))
    )
    (net (code "112") (name "/PB12") (class "Default")
      (node (ref "H2") (pin "13") (pinfunction "13_13") (pintype "input"))
      (node (ref "U1") (pin "P12") (pinfunction "PB12_P12") (pintype "unspecified"))
    )
    (net (code "113") (name "/PB13") (class "Default")
      (node (ref "H2") (pin "14") (pinfunction "14_14") (pintype "input"))
      (node (ref "U1") (pin "P13") (pinfunction "PB13_P13") (pintype "unspecified"))
    )
    (net (code "114") (name "/PC0") (class "Default")
      (node (ref "H5") (pin "4") (pinfunction "4_4") (pintype "input"))
      (node (ref "U1") (pin "M2") (pinfunction "PC0_M2") (pintype "unspecified"))
    )
    (net (code "115") (name "/PC1") (class "Default")
      (node (ref "H5") (pin "3") (pinfunction "3_3") (pintype "input"))
      (node (ref "U1") (pin "M3") (pinfunction "PC1_M3") (pintype "unspecified"))
    )
    (net (code "116") (name "/PC4") (class "Default")
      (node (ref "H1") (pin "13") (pinfunction "13_13") (pintype "input"))
      (node (ref "U1") (pin "N5") (pinfunction "PC4_N5") (pintype "unspecified"))
    )
    (net (code "117") (name "/PC5") (class "Default")
      (node (ref "H2") (pin "16") (pinfunction "16_16") (pintype "input"))
      (node (ref "U1") (pin "P5") (pinfunction "PC5_P5") (pintype "unspecified"))
    )
    (net (code "118") (name "/PC13") (class "Default")
      (node (ref "H1") (pin "12") (pinfunction "12_12") (pintype "input"))
      (node (ref "U1") (pin "D1") (pinfunction "PC13_D1") (pintype "unspecified"))
    )
    (net (code "119") (name "/PC14") (class "Default")
      (node (ref "H1") (pin "8") (pinfunction "8_8") (pintype "input"))
      (node (ref "U1") (pin "E1") (pinfunction "PC14_E1") (pintype "unspecified"))
    )
    (net (code "120") (name "/PC15") (class "Default")
      (node (ref "H1") (pin "9") (pinfunction "9_9") (pintype "input"))
      (node (ref "U1") (pin "F1") (pinfunction "PC15_F1") (pintype "unspecified"))
    )
    (net (code "121") (name "/PD5") (class "Default")
      (node (ref "H2") (pin "3") (pinfunction "3_3") (pintype "input"))
      (node (ref "U1") (pin "C11") (pinfunction "PD5_C11") (pintype "unspecified"))
    )
    (net (code "122") (name "/PD11") (class "Default")
      (node (ref "H2") (pin "11") (pinfunction "11_11") (pintype "input"))
      (node (ref "U1") (pin "N14") (pinfunction "PD11_N14") (pintype "unspecified"))
    )
    (net (code "123") (name "/PD12") (class "Default")
      (node (ref "H2") (pin "12") (pinfunction "12_12") (pintype "input"))
      (node (ref "U1") (pin "N13") (pinfunction "PD12_N13") (pintype "unspecified"))
    )
    (net (code "124") (name "/PD13") (class "Default")
      (node (ref "H2") (pin "10") (pinfunction "10_10") (pintype "input"))
      (node (ref "U1") (pin "M15") (pinfunction "PD13_M15") (pintype "unspecified"))
    )
    (net (code "125") (name "/PE0") (class "Default")
      (node (ref "H1") (pin "16") (pinfunction "16_16") (pintype "input"))
      (node (ref "U1") (pin "A4") (pinfunction "PE0_A4") (pintype "unspecified"))
    )
    (net (code "126") (name "/PE1") (class "Default")
      (node (ref "H1") (pin "14") (pinfunction "14_14") (pintype "input"))
      (node (ref "U1") (pin "A3") (pinfunction "PE1_A3") (pintype "unspecified"))
    )
    (net (code "127") (name "/PE2") (class "Default")
      (node (ref "H1") (pin "5") (pinfunction "5_5") (pintype "input"))
      (node (ref "U1") (pin "A2") (pinfunction "PE2_A2") (pintype "unspecified"))
    )
    (net (code "128") (name "/PE3") (class "Default")
      (node (ref "H1") (pin "4") (pinfunction "4_4") (pintype "input"))
      (node (ref "U1") (pin "A1") (pinfunction "PE3_A1") (pintype "unspecified"))
    )
    (net (code "129") (name "/PG9") (class "Default")
      (node (ref "H2") (pin "6") (pinfunction "6_6") (pintype "input"))
      (node (ref "U1") (pin "C10") (pinfunction "PG9_C10") (pintype "unspecified"))
    )
    (net (code "130") (name "/PG13") (class "Default")
      (node (ref "H2") (pin "1") (pinfunction "1_1") (pintype "input"))
      (node (ref "U1") (pin "A8") (pinfunction "PG13_A8") (pintype "unspecified"))
    )
    (net (code "131") (name "/PG14") (class "Default")
      (node (ref "H2") (pin "2") (pinfunction "2_2") (pintype "input"))
      (node (ref "U1") (pin "A7") (pinfunction "PG14_A7") (pintype "unspecified"))
    )
    (net (code "132") (name "/PH6") (class "Default")
      (node (ref "H2") (pin "9") (pinfunction "9_9") (pintype "input"))
      (node (ref "U1") (pin "M11") (pinfunction "PH6_M11") (pintype "unspecified"))
    )
    (net (code "133") (name "/PI8") (class "Default")
      (node (ref "H5") (pin "5") (pinfunction "5_5") (pintype "input"))
      (node (ref "U1") (pin "D2") (pinfunction "PI8_D2") (pintype "unspecified"))
    )
    (net (code "134") (name "/PI11") (class "Default")
      (node (ref "H1") (pin "11") (pinfunction "11_11") (pintype "input"))
      (node (ref "U1") (pin "E4") (pinfunction "PI11_E4") (pintype "unspecified"))
    )
    (net (code "135") (name "/SDIO_CLK") (class "Default")
      (node (ref "MICRO-SD") (pin "5") (pinfunction "CLK_5") (pintype "input"))
      (node (ref "R19") (pin "1") (pinfunction "1_1") (pintype "input"))
      (node (ref "U1") (pin "A12") (pinfunction "PC12_A12") (pintype "unspecified"))
    )
    (net (code "136") (name "/SDIO_CMD") (class "Default")
      (node (ref "MICRO-SD") (pin "3") (pinfunction "CMD_3") (pintype "input"))
      (node (ref "R18") (pin "1") (pinfunction "1_1") (pintype "input"))
      (node (ref "U1") (pin "D12") (pinfunction "PD2_D12") (pintype "unspecified"))
    )
    (net (code "137") (name "/SDIO_D0") (class "Default")
      (node (ref "MICRO-SD") (pin "7") (pinfunction "DAT0_7") (pintype "input"))
      (node (ref "R20") (pin "1") (pinfunction "1_1") (pintype "input"))
      (node (ref "U1") (pin "G14") (pinfunction "PC8_G14") (pintype "unspecified"))
    )
    (net (code "138") (name "/SDIO_D1") (class "Default")
      (node (ref "MICRO-SD") (pin "8") (pinfunction "DAT1_8") (pintype "input"))
      (node (ref "R21") (pin "1") (pinfunction "1_1") (pintype "input"))
      (node (ref "U1") (pin "F14") (pinfunction "PC9_F14") (pintype "unspecified"))
    )
    (net (code "139") (name "/SDIO_D2") (class "Default")
      (node (ref "MICRO-SD") (pin "1") (pinfunction "DAT2_1") (pintype "input"))
      (node (ref "R16") (pin "1") (pinfunction "1_1") (pintype "input"))
      (node (ref "U1") (pin "E15") (pinfunction "PA9_E15") (pintype "unspecified"))
    )
    (net (code "140") (name "/SDIO_D3") (class "Default")
      (node (ref "MICRO-SD") (pin "2") (pinfunction "CD/DAT3_2") (pintype "input"))
      (node (ref "R17") (pin "1") (pinfunction "1_1") (pintype "input"))
      (node (ref "U1") (pin "B13") (pinfunction "PC11_B13") (pintype "unspecified"))
    )
    (net (code "141") (name "/SDIO_DET") (class "Default")
      (node (ref "MICRO-SD") (pin "9") (pinfunction "CARD_DET_9") (pintype "input"))
      (node (ref "R22") (pin "1") (pinfunction "1_1") (pintype "input"))
      (node (ref "U1") (pin "D10") (pinfunction "PD4_D10") (pintype "unspecified"))
    )
    (net (code "142") (name "/SWCLK") (class "Default")
      (node (ref "H3") (pin "4") (pinfunction "4_4") (pintype "input"))
      (node (ref "U1") (pin "A14") (pinfunction "PA14_A14") (pintype "unspecified"))
    )
    (net (code "143") (name "/SWDIO") (class "Default")
      (node (ref "H3") (pin "3") (pinfunction "3_3") (pintype "input"))
      (node (ref "U1") (pin "A15") (pinfunction "PA13_A15") (pintype "unspecified"))
    )
    (net (code "144") (name "/UART_RX") (class "Default")
      (node (ref "U1") (pin "A10") (pinfunction "PB3_A10") (pintype "unspecified"))
      (node (ref "U4") (pin "8") (pinfunction "TXD_8") (pintype "unspecified"))
    )
    (net (code "145") (name "/UART_TX") (class "Default")
      (node (ref "U1") (pin "A13") (pinfunction "PA15_A13") (pintype "unspecified"))
      (node (ref "U4") (pin "9") (pinfunction "RXD_9") (pintype "unspecified"))
    )
    (net (code "146") (name "/USB_DN") (class "Default")
      (node (ref "U1") (pin "R14") (pinfunction "PB14_R14") (pintype "unspecified"))
      (node (ref "USB_HS") (pin "5") (pinfunction "DN2_5") (pintype "unspecified"))
      (node (ref "USB_HS") (pin "7") (pinfunction "DN1_7") (pintype "unspecified"))
    )
    (net (code "147") (name "/USB_DP") (class "Default")
      (node (ref "U1") (pin "R15") (pinfunction "PB15_R15") (pintype "unspecified"))
      (node (ref "USB_HS") (pin "6") (pinfunction "DP1_6") (pintype "unspecified"))
      (node (ref "USB_HS") (pin "8") (pinfunction "DP2_8") (pintype "unspecified"))
    )
    (net (code "148") (name "/VO+") (class "Default")
      (node (ref "H4") (pin "2") (pinfunction "2_2") (pintype "input"))
      (node (ref "R32") (pin "1") (pinfunction "1_1") (pintype "input"))
      (node (ref "U6") (pin "5") (pinfunction "VO+_5") (pintype "unspecified"))
    )
    (net (code "149") (name "/VO-") (class "Default")
      (node (ref "H4") (pin "1") (pinfunction "1_1") (pintype "input"))
      (node (ref "R32") (pin "2") (pinfunction "2_2") (pintype "input"))
      (node (ref "U6") (pin "8") (pinfunction "VO-_8") (pintype "unspecified"))
    )
    (net (code "150") (name "3V3") (class "Default")
      (node (ref "C1") (pin "2") (pinfunction "2_2") (pintype "input"))
      (node (ref "C10") (pin "2") (pinfunction "2_2") (pintype "input"))
      (node (ref "C11") (pin "2") (pinfunction "2_2") (pintype "input"))
      (node (ref "C12") (pin "2") (pinfunction "2_2") (pintype "input"))
      (node (ref "C13") (pin "2") (pinfunction "2_2") (pintype "input"))
      (node (ref "C14") (pin "2") (pinfunction "2_2") (pintype "input"))
      (node (ref "C15") (pin "2") (pinfunction "2_2") (pintype "input"))
      (node (ref "C16") (pin "2") (pinfunction "2_2") (pintype "input"))
      (node (ref "C19") (pin "2") (pinfunction "2_2") (pintype "input"))
      (node (ref "C2") (pin "2") (pinfunction "2_2") (pintype "input"))
      (node (ref "C20") (pin "2") (pinfunction "2_2") (pintype "input"))
      (node (ref "C27") (pin "2") (pinfunction "2_2") (pintype "input"))
      (node (ref "C28") (pin "2") (pinfunction "2_2") (pintype "input"))
      (node (ref "C29") (pin "2") (pinfunction "2_2") (pintype "input"))
      (node (ref "C3") (pin "2") (pinfunction "2_2") (pintype "input"))
      (node (ref "C31") (pin "1") (pinfunction "1_1") (pintype "input"))
      (node (ref "C32") (pin "2") (pinfunction "2_2") (pintype "input"))
      (node (ref "C37") (pin "2") (pinfunction "2_2") (pintype "input"))
      (node (ref "C39") (pin "2") (pinfunction "2_2") (pintype "input"))
      (node (ref "C4") (pin "2") (pinfunction "2_2") (pintype "input"))
      (node (ref "C40") (pin "2") (pinfunction "2_2") (pintype "input"))
      (node (ref "C5") (pin "2") (pinfunction "2_2") (pintype "input"))
      (node (ref "C6") (pin "2") (pinfunction "2_2") (pintype "input"))
      (node (ref "C7") (pin "2") (pinfunction "2_2") (pintype "input"))
      (node (ref "C8") (pin "2") (pinfunction "2_2") (pintype "input"))
      (node (ref "C9") (pin "2") (pinfunction "2_2") (pintype "input"))
      (node (ref "H1") (pin "10") (pinfunction "10_10") (pintype "input"))
      (node (ref "H1") (pin "6") (pinfunction "6_6") (pintype "input"))
      (node (ref "H2") (pin "8") (pinfunction "8_8") (pintype "input"))
      (node (ref "H3") (pin "1") (pinfunction "1_1") (pintype "input"))
      (node (ref "H5") (pin "2") (pinfunction "2_2") (pintype "input"))
      (node (ref "L1") (pin "1") (pinfunction "1_1") (pintype "unspecified"))
      (node (ref "LCD") (pin "4") (pinfunction "4_4") (pintype "unspecified"))
      (node (ref "MICRO-SD") (pin "4") (pinfunction "VDD_4") (pintype "input"))
      (node (ref "R1") (pin "2") (pinfunction "2_2") (pintype "input"))
      (node (ref "R10") (pin "2") (pinfunction "2_2") (pintype "input"))
      (node (ref "R11") (pin "1") (pinfunction "1_1") (pintype "input"))
      (node (ref "R12") (pin "1") (pinfunction "1_1") (pintype "input"))
      (node (ref "R13") (pin "2") (pinfunction "2_2") (pintype "input"))
      (node (ref "R14") (pin "2") (pinfunction "2_2") (pintype "input"))
      (node (ref "R16") (pin "2") (pinfunction "2_2") (pintype "input"))
      (node (ref "R17") (pin "2") (pinfunction "2_2") (pintype "input"))
      (node (ref "R18") (pin "2") (pinfunction "2_2") (pintype "input"))
      (node (ref "R19") (pin "2") (pinfunction "2_2") (pintype "input"))
      (node (ref "R20") (pin "2") (pinfunction "2_2") (pintype "input"))
      (node (ref "R21") (pin "2") (pinfunction "2_2") (pintype "input"))
      (node (ref "R22") (pin "2") (pinfunction "2_2") (pintype "input"))
      (node (ref "R31") (pin "1") (pinfunction "1_1") (pintype "input"))
      (node (ref "R7") (pin "2") (pinfunction "2_2") (pintype "input"))
      (node (ref "R8") (pin "2") (pinfunction "2_2") (pintype "input"))
      (node (ref "R9") (pin "2") (pinfunction "2_2") (pintype "input"))
      (node (ref "U1") (pin "C1") (pinfunction "VBAT_C1") (pintype "unspecified"))
      (node (ref "U1") (pin "C5") (pinfunction "VDD_C5") (pintype "unspecified"))
      (node (ref "U1") (pin "C6") (pinfunction "PDR_ON_C6") (pintype "unspecified"))
      (node (ref "U1") (pin "C7") (pinfunction "VDD_C7") (pintype "unspecified"))
      (node (ref "U1") (pin "C8") (pinfunction "VDD_C8") (pintype "unspecified"))
      (node (ref "U1") (pin "C9") (pinfunction "VDD_C9") (pintype "unspecified"))
      (node (ref "U1") (pin "F3") (pinfunction "VDD_F3") (pintype "unspecified"))
      (node (ref "U1") (pin "G13") (pinfunction "VDD_G13") (pintype "unspecified"))
      (node (ref "U1") (pin "G3") (pinfunction "VDD_G3") (pintype "unspecified"))
      (node (ref "U1") (pin "H13") (pinfunction "VDD_H13") (pintype "unspecified"))
      (node (ref "U1") (pin "J12") (pinfunction "VDD_J12") (pintype "unspecified"))
      (node (ref "U1") (pin "J13") (pinfunction "VDD_J13") (pintype "unspecified"))
      (node (ref "U1") (pin "K4") (pinfunction "VDD_K4") (pintype "unspecified"))
      (node (ref "U1") (pin "N10") (pinfunction "VDD_N10") (pintype "unspecified"))
      (node (ref "U1") (pin "N8") (pinfunction "VDD_N8") (pintype "unspecified"))
      (node (ref "U1") (pin "N9") (pinfunction "VDD_N9") (pintype "unspecified"))
      (node (ref "U1") (pin "P1") (pinfunction "VREF+_P1") (pintype "unspecified"))
      (node (ref "U1") (pin "R1") (pinfunction "VDDA_R1") (pintype "unspecified"))
      (node (ref "U2") (pin "A7") (pinfunction "VDD_A7") (pintype "input"))
      (node (ref "U2") (pin "B2") (pinfunction "VDDQ_B2") (pintype "input"))
      (node (ref "U2") (pin "B7") (pinfunction "VDDQ_B7") (pintype "input"))
      (node (ref "U2") (pin "C9") (pinfunction "VDDQ_C9") (pintype "input"))
      (node (ref "U2") (pin "D9") (pinfunction "VDDQ_D9") (pintype "input"))
      (node (ref "U2") (pin "E1") (pinfunction "VDDQ_E1") (pintype "input"))
      (node (ref "U2") (pin "F9") (pinfunction "VDD_F9") (pintype "input"))
      (node (ref "U2") (pin "L1") (pinfunction "VDDQ_L1") (pintype "input"))
      (node (ref "U2") (pin "L7") (pinfunction "VDD_L7") (pintype "input"))
      (node (ref "U2") (pin "M9") (pinfunction "VDDQ_M9") (pintype "input"))
      (node (ref "U2") (pin "N9") (pinfunction "VDDQ_N9") (pintype "input"))
      (node (ref "U2") (pin "P2") (pinfunction "VDDQ_P2") (pintype "input"))
      (node (ref "U2") (pin "P7") (pinfunction "VDDQ_P7") (pintype "input"))
      (node (ref "U2") (pin "R7") (pinfunction "VDD_R7") (pintype "input"))
      (node (ref "U3") (pin "2") (pinfunction "VOUT(TAB)_2") (pintype "unspecified"))
      (node (ref "U3") (pin "4") (pinfunction "TAB_4") (pintype "unspecified"))
      (node (ref "U4") (pin "10") (pinfunction "V3_10") (pintype "unspecified"))
      (node (ref "U4") (pin "7") (pinfunction "VCC_7") (pintype "unspecified"))
      (node (ref "U5") (pin "8") (pinfunction "VCC_8") (pintype "input"))
      (node (ref "U6") (pin "6") (pinfunction "VDD_6") (pintype "unspecified"))
      (node (ref "U7") (pin "5") (pinfunction "VIN_5") (pintype "unspecified"))
    )
    (net (code "151") (name "5V") (class "Default")
      (node (ref "C21") (pin "2") (pinfunction "2_2") (pintype "input"))
      (node (ref "C22") (pin "2") (pinfunction "2_2") (pintype "input"))
      (node (ref "R33") (pin "2") (pinfunction "2_2") (pintype "input"))
      (node (ref "R34") (pin "2") (pinfunction "2_2") (pintype "input"))
      (node (ref "U3") (pin "3") (pinfunction "VIN_3") (pintype "unspecified"))
      (node (ref "USB_HS") (pin "11") (pinfunction "VBUS_11") (pintype "unspecified"))
      (node (ref "USB_HS") (pin "2") (pinfunction "VBUS_2") (pintype "unspecified"))
      (node (ref "USB_UART") (pin "11") (pinfunction "VBUS_11") (pintype "unspecified"))
      (node (ref "USB_UART") (pin "2") (pinfunction "VBUS_2") (pintype "unspecified"))
    )
    (net (code "152") (name "GND") (class "Default")
      (node (ref "C1") (pin "1") (pinfunction "1_1") (pintype "input"))
      (node (ref "C10") (pin "1") (pinfunction "1_1") (pintype "input"))
      (node (ref "C11") (pin "1") (pinfunction "1_1") (pintype "input"))
      (node (ref "C12") (pin "1") (pinfunction "1_1") (pintype "input"))
      (node (ref "C13") (pin "1") (pinfunction "1_1") (pintype "input"))
      (node (ref "C14") (pin "1") (pinfunction "1_1") (pintype "input"))
      (node (ref "C15") (pin "1") (pinfunction "1_1") (pintype "input"))
      (node (ref "C16") (pin "1") (pinfunction "1_1") (pintype "input"))
      (node (ref "C17") (pin "2") (pinfunction "2_2") (pintype "input"))
      (node (ref "C18") (pin "2") (pinfunction "2_2") (pintype "input"))
      (node (ref "C19") (pin "1") (pinfunction "1_1") (pintype "input"))
      (node (ref "C2") (pin "1") (pinfunction "1_1") (pintype "input"))
      (node (ref "C20") (pin "1") (pinfunction "1_1") (pintype "input"))
      (node (ref "C21") (pin "1") (pinfunction "1_1") (pintype "input"))
      (node (ref "C22") (pin "1") (pinfunction "1_1") (pintype "input"))
      (node (ref "C23") (pin "1") (pinfunction "1_1") (pintype "input"))
      (node (ref "C24") (pin "1") (pinfunction "1_1") (pintype "input"))
      (node (ref "C25") (pin "1") (pinfunction "1_1") (pintype "input"))
      (node (ref "C26") (pin "1") (pinfunction "1_1") (pintype "input"))
      (node (ref "C27") (pin "1") (pinfunction "1_1") (pintype "input"))
      (node (ref "C28") (pin "1") (pinfunction "1_1") (pintype "input"))
      (node (ref "C29") (pin "1") (pinfunction "1_1") (pintype "input"))
      (node (ref "C3") (pin "1") (pinfunction "1_1") (pintype "input"))
      (node (ref "C30") (pin "1") (pinfunction "1_1") (pintype "input"))
      (node (ref "C31") (pin "2") (pinfunction "2_2") (pintype "input"))
      (node (ref "C32") (pin "1") (pinfunction "1_1") (pintype "input"))
      (node (ref "C33") (pin "1") (pinfunction "1_1") (pintype "input"))
      (node (ref "C35") (pin "1") (pinfunction "1_1") (pintype "input"))
      (node (ref "C36") (pin "1") (pinfunction "1_1") (pintype "input"))
      (node (ref "C37") (pin "1") (pinfunction "1_1") (pintype "input"))
      (node (ref "C38") (pin "2") (pinfunction "2_2") (pintype "input"))
      (node (ref "C39") (pin "1") (pinfunction "1_1") (pintype "input"))
      (node (ref "C4") (pin "1") (pinfunction "1_1") (pintype "input"))
      (node (ref "C40") (pin "1") (pinfunction "1_1") (pintype "input"))
      (node (ref "C5") (pin "1") (pinfunction "1_1") (pintype "input"))
      (node (ref "C6") (pin "1") (pinfunction "1_1") (pintype "input"))
      (node (ref "C7") (pin "1") (pinfunction "1_1") (pintype "input"))
      (node (ref "C8") (pin "1") (pinfunction "1_1") (pintype "input"))
      (node (ref "C9") (pin "1") (pinfunction "1_1") (pintype "input"))
      (node (ref "H1") (pin "3") (pinfunction "3_3") (pintype "input"))
      (node (ref "H1") (pin "7") (pinfunction "7_7") (pintype "input"))
      (node (ref "H2") (pin "7") (pinfunction "7_7") (pintype "input"))
      (node (ref "H3") (pin "2") (pinfunction "2_2") (pintype "input"))
      (node (ref "H5") (pin "1") (pinfunction "1_1") (pintype "input"))
      (node (ref "KEY1") (pin "1") (pinfunction "1_1") (pintype "input"))
      (node (ref "KEY2") (pin "1") (pinfunction "1_1") (pintype "input"))
      (node (ref "KEY3") (pin "1") (pinfunction "1_1") (pintype "input"))
      (node (ref "LCD") (pin "29") (pinfunction "29_29") (pintype "unspecified"))
      (node (ref "LCD") (pin "3") (pinfunction "3_3") (pintype "unspecified"))
      (node (ref "LCD") (pin "36") (pinfunction "36_36") (pintype "unspecified"))
      (node (ref "LCD") (pin "41") (pinfunction "41_41") (pintype "unspecified"))
      (node (ref "LCD") (pin "42") (pinfunction "42_42") (pintype "unspecified"))
      (node (ref "LED1") (pin "1") (pinfunction "C_1") (pintype "input"))
      (node (ref "LED2") (pin "1") (pinfunction "C_1") (pintype "input"))
      (node (ref "MICRO-SD") (pin "10") (pinfunction "GND_10") (pintype "input"))
      (node (ref "MICRO-SD") (pin "11") (pinfunction "GND_11") (pintype "input"))
      (node (ref "MICRO-SD") (pin "12") (pinfunction "GND_12") (pintype "input"))
      (node (ref "MICRO-SD") (pin "13") (pinfunction "GND_13") (pintype "input"))
      (node (ref "MICRO-SD") (pin "6") (pinfunction "VSS_6") (pintype "input"))
      (node (ref "R15") (pin "2") (pinfunction "2_2") (pintype "input"))
      (node (ref "R3") (pin "1") (pinfunction "1_1") (pintype "input"))
      (node (ref "R4") (pin "1") (pinfunction "1_1") (pintype "input"))
      (node (ref "R5") (pin "1") (pinfunction "1_1") (pintype "input"))
      (node (ref "R6") (pin "1") (pinfunction "1_1") (pintype "input"))
      (node (ref "RST") (pin "5") (pinfunction "5_5") (pintype "unspecified"))
      (node (ref "U1") (pin "D5") (pinfunction "VSS_D5") (pintype "unspecified"))
      (node (ref "U1") (pin "D6") (pinfunction "BOOT0_D6") (pintype "unspecified"))
      (node (ref "U1") (pin "D7") (pinfunction "VSS_D7") (pintype "unspecified"))
      (node (ref "U1") (pin "D8") (pinfunction "VSS_D8") (pintype "unspecified"))
      (node (ref "U1") (pin "D9") (pinfunction "VSS_D9") (pintype "unspecified"))
      (node (ref "U1") (pin "F10") (pinfunction "VSS_F10") (pintype "unspecified"))
      (node (ref "U1") (pin "F12") (pinfunction "VSS_F12") (pintype "unspecified"))
      (node (ref "U1") (pin "F2") (pinfunction "VSS_F2") (pintype "unspecified"))
      (node (ref "U1") (pin "F6") (pinfunction "VSS_F6") (pintype "unspecified"))
      (node (ref "U1") (pin "F7") (pinfunction "VSS_F7") (pintype "unspecified"))
      (node (ref "U1") (pin "F8") (pinfunction "VSS_F8") (pintype "unspecified"))
      (node (ref "U1") (pin "F9") (pinfunction "VSS_F9") (pintype "unspecified"))
      (node (ref "U1") (pin "G10") (pinfunction "VSS_G10") (pintype "unspecified"))
      (node (ref "U1") (pin "G12") (pinfunction "VSS_G12") (pintype "unspecified"))
      (node (ref "U1") (pin "G2") (pinfunction "VSS_G2") (pintype "unspecified"))
      (node (ref "U1") (pin "G6") (pinfunction "VSS_G6") (pintype "unspecified"))
      (node (ref "U1") (pin "G7") (pinfunction "VSS_G7") (pintype "unspecified"))
      (node (ref "U1") (pin "G8") (pinfunction "VSS_G8") (pintype "unspecified"))
      (node (ref "U1") (pin "G9") (pinfunction "VSS_G9") (pintype "unspecified"))
      (node (ref "U1") (pin "H10") (pinfunction "VSS_H10") (pintype "unspecified"))
      (node (ref "U1") (pin "H12") (pinfunction "VSS_H12") (pintype "unspecified"))
      (node (ref "U1") (pin "H6") (pinfunction "VSS_H6") (pintype "unspecified"))
      (node (ref "U1") (pin "H7") (pinfunction "VSS_H7") (pintype "unspecified"))
      (node (ref "U1") (pin "H8") (pinfunction "VSS_H8") (pintype "unspecified"))
      (node (ref "U1") (pin "H9") (pinfunction "VSS_H9") (pintype "unspecified"))
      (node (ref "U1") (pin "J10") (pinfunction "VSS_J10") (pintype "unspecified"))
      (node (ref "U1") (pin "J6") (pinfunction "VSS_J6") (pintype "unspecified"))
      (node (ref "U1") (pin "J7") (pinfunction "VSS_J7") (pintype "unspecified"))
      (node (ref "U1") (pin "J8") (pinfunction "VSS_J8") (pintype "unspecified"))
      (node (ref "U1") (pin "J9") (pinfunction "VSS_J9") (pintype "unspecified"))
      (node (ref "U1") (pin "K10") (pinfunction "VSS_K10") (pintype "unspecified"))
      (node (ref "U1") (pin "K6") (pinfunction "VSS_K6") (pintype "unspecified"))
      (node (ref "U1") (pin "K7") (pinfunction "VSS_K7") (pintype "unspecified"))
      (node (ref "U1") (pin "K8") (pinfunction "VSS_K8") (pintype "unspecified"))
      (node (ref "U1") (pin "K9") (pinfunction "VSS_K9") (pintype "unspecified"))
      (node (ref "U1") (pin "M1") (pinfunction "VSSA_M1") (pintype "unspecified"))
      (node (ref "U1") (pin "M8") (pinfunction "VSS_M8") (pintype "unspecified"))
      (node (ref "U1") (pin "M9") (pinfunction "VSS_M9") (pintype "unspecified"))
      (node (ref "U1") (pin "N1") (pinfunction "VREF-_N1") (pintype "unspecified"))
      (node (ref "U2") (pin "A3") (pinfunction "VSS_A3") (pintype "input"))
      (node (ref "U2") (pin "B3") (pinfunction "VSSQ_B3") (pintype "input"))
      (node (ref "U2") (pin "B8") (pinfunction "VSSQ_B8") (pintype "input"))
      (node (ref "U2") (pin "C1") (pinfunction "VSSQ_C1") (pintype "input"))
      (node (ref "U2") (pin "D1") (pinfunction "VSSQ_D1") (pintype "input"))
      (node (ref "U2") (pin "E9") (pinfunction "VSSQ_E9") (pintype "input"))
      (node (ref "U2") (pin "F1") (pinfunction "VSS_F1") (pintype "input"))
      (node (ref "U2") (pin "F2") (pinfunction "DQM3_F2") (pintype "input"))
      (node (ref "U2") (pin "F8") (pinfunction "DQM2_F8") (pintype "input"))
      (node (ref "U2") (pin "K1") (pinfunction "DQM1_K1") (pintype "input"))
      (node (ref "U2") (pin "K9") (pinfunction "DQM0_K9") (pintype "input"))
      (node (ref "U2") (pin "L3") (pinfunction "VSS_L3") (pintype "input"))
      (node (ref "U2") (pin "L9") (pinfunction "VSSQ_L9") (pintype "input"))
      (node (ref "U2") (pin "M1") (pinfunction "VSSQ_M1") (pintype "input"))
      (node (ref "U2") (pin "N1") (pinfunction "VSSQ_N1") (pintype "input"))
      (node (ref "U2") (pin "P3") (pinfunction "VSSQ_P3") (pintype "input"))
      (node (ref "U2") (pin "P8") (pinfunction "VSSQ_P8") (pintype "input"))
      (node (ref "U2") (pin "R3") (pinfunction "VSS_R3") (pintype "input"))
      (node (ref "U3") (pin "1") (pinfunction "ADJ(GND)_1") (pintype "unspecified"))
      (node (ref "U4") (pin "3") (pinfunction "GND_3") (pintype "unspecified"))
      (node (ref "U5") (pin "4") (pinfunction "VSS_4") (pintype "input"))
      (node (ref "U6") (pin "7") (pinfunction "GND_7") (pintype "unspecified"))
      (node (ref "U7") (pin "2") (pinfunction "GND_2") (pintype "unspecified"))
      (node (ref "USB_HS") (pin "1") (pinfunction "GND_1") (pintype "unspecified"))
      (node (ref "USB_HS") (pin "12") (pinfunction "GND_12") (pintype "unspecified"))
      (node (ref "USB_HS") (pin "13") (pinfunction "SHELL_13") (pintype "unspecified"))
      (node (ref "USB_HS") (pin "14") (pinfunction "SHELL_14") (pintype "unspecified"))
      (node (ref "USB_UART") (pin "1") (pinfunction "GND_1") (pintype "unspecified"))
      (node (ref "USB_UART") (pin "12") (pinfunction "GND_12") (pintype "unspecified"))
      (node (ref "USB_UART") (pin "13") (pinfunction "SHELL_13") (pintype "unspecified"))
      (node (ref "USB_UART") (pin "14") (pinfunction "SHELL_14") (pintype "unspecified"))
      (node (ref "X1") (pin "2") (pinfunction "GND_2") (pintype "input"))
      (node (ref "X1") (pin "4") (pinfunction "GND_4") (pintype "input"))
    )
    (net (code "153") (name "Net-(C23-Pad2)") (class "Default")
      (node (ref "C23") (pin "2") (pinfunction "2_2") (pintype "input"))
      (node (ref "R27") (pin "2") (pinfunction "2_2") (pintype "input"))
      (node (ref "R7") (pin "1") (pinfunction "1_1") (pintype "input"))
      (node (ref "RST") (pin "4") (pinfunction "4_4") (pintype "unspecified"))
    )
    (net (code "154") (name "Net-(C24-Pad2)") (class "Default")
      (node (ref "C24") (pin "2") (pinfunction "2_2") (pintype "input"))
      (node (ref "KEY1") (pin "2") (pinfunction "2_2") (pintype "input"))
      (node (ref "R28") (pin "2") (pinfunction "2_2") (pintype "input"))
      (node (ref "R8") (pin "1") (pinfunction "1_1") (pintype "input"))
    )
    (net (code "155") (name "Net-(C25-Pad2)") (class "Default")
      (node (ref "C25") (pin "2") (pinfunction "2_2") (pintype "input"))
      (node (ref "KEY2") (pin "2") (pinfunction "2_2") (pintype "input"))
      (node (ref "R29") (pin "2") (pinfunction "2_2") (pintype "input"))
      (node (ref "R9") (pin "1") (pinfunction "1_1") (pintype "input"))
    )
    (net (code "156") (name "Net-(C26-Pad2)") (class "Default")
      (node (ref "C26") (pin "2") (pinfunction "2_2") (pintype "input"))
      (node (ref "KEY3") (pin "2") (pinfunction "2_2") (pintype "input"))
      (node (ref "R10") (pin "1") (pinfunction "1_1") (pintype "input"))
      (node (ref "R30") (pin "2") (pinfunction "2_2") (pintype "input"))
    )
    (net (code "157") (name "Net-(C33-Pad2)") (class "Default")
      (node (ref "C33") (pin "2") (pinfunction "2_2") (pintype "input"))
      (node (ref "R23") (pin "1") (pinfunction "1_1") (pintype "input"))
    )
    (net (code "158") (name "Net-(C34-Pad1)") (class "Default")
      (node (ref "C34") (pin "1") (pinfunction "1_1") (pintype "input"))
      (node (ref "C36") (pin "2") (pinfunction "2_2") (pintype "input"))
      (node (ref "R26") (pin "2") (pinfunction "2_2") (pintype "input"))
    )
    (net (code "159") (name "Net-(C34-Pad2)") (class "Default")
      (node (ref "C34") (pin "2") (pinfunction "2_2") (pintype "input"))
      (node (ref "R24") (pin "1") (pinfunction "1_1") (pintype "input"))
    )
    (net (code "160") (name "Net-(C35-Pad2)") (class "Default")
      (node (ref "C35") (pin "2") (pinfunction "2_2") (pintype "input"))
      (node (ref "R25") (pin "2") (pinfunction "2_2") (pintype "input"))
      (node (ref "R26") (pin "1") (pinfunction "1_1") (pintype "input"))
    )
    (net (code "161") (name "Net-(D1-A)") (class "Default")
      (node (ref "D1") (pin "1") (pinfunction "A_1") (pintype "unspecified"))
      (node (ref "L1") (pin "2") (pinfunction "2_2") (pintype "unspecified"))
      (node (ref "U7") (pin "1") (pinfunction "SW_1") (pintype "unspecified"))
    )
    (net (code "162") (name "Net-(LED1-A)") (class "Default")
      (node (ref "LED1") (pin "2") (pinfunction "A_2") (pintype "input"))
      (node (ref "R1") (pin "1") (pinfunction "1_1") (pintype "input"))
    )
    (net (code "163") (name "Net-(LED2-A)") (class "Default")
      (node (ref "LED2") (pin "2") (pinfunction "A_2") (pintype "input"))
      (node (ref "R2") (pin "1") (pinfunction "1_1") (pintype "input"))
    )
    (net (code "164") (name "Net-(U6-IN+)") (class "Default")
      (node (ref "R23") (pin "2") (pinfunction "2_2") (pintype "input"))
      (node (ref "U6") (pin "3") (pinfunction "IN+_3") (pintype "unspecified"))
    )
    (net (code "165") (name "Net-(U6-IN-)") (class "Default")
      (node (ref "R24") (pin "2") (pinfunction "2_2") (pintype "input"))
      (node (ref "U6") (pin "4") (pinfunction "IN-_4") (pintype "unspecified"))
    )
    (net (code "166") (name "Net-(U6-NC)") (class "Default")
      (node (ref "C38") (pin "1") (pinfunction "1_1") (pintype "input"))
      (node (ref "U6") (pin "2") (pinfunction "NC_2") (pintype "unspecified"))
    )
    (net (code "167") (name "Net-(USB_HS-CC1)") (class "Default")
      (node (ref "R3") (pin "2") (pinfunction "2_2") (pintype "input"))
      (node (ref "R33") (pin "1") (pinfunction "1_1") (pintype "input"))
      (node (ref "USB_HS") (pin "4") (pinfunction "CC1_4") (pintype "unspecified"))
    )
    (net (code "168") (name "Net-(USB_HS-CC2)") (class "Default")
      (node (ref "R34") (pin "1") (pinfunction "1_1") (pintype "input"))
      (node (ref "R4") (pin "2") (pinfunction "2_2") (pintype "input"))
      (node (ref "USB_HS") (pin "10") (pinfunction "CC2_10") (pintype "unspecified"))
    )
    (net (code "169") (name "Net-(USB_UART-CC1)") (class "Default")
      (node (ref "R5") (pin "2") (pinfunction "2_2") (pintype "input"))
      (node (ref "USB_UART") (pin "4") (pinfunction "CC1_4") (pintype "unspecified"))
    )
    (net (code "170") (name "Net-(USB_UART-CC2)") (class "Default")
      (node (ref "R6") (pin "2") (pinfunction "2_2") (pintype "input"))
      (node (ref "USB_UART") (pin "10") (pinfunction "CC2_10") (pintype "unspecified"))
    )
    (net (code "171") (name "unconnected-(LCD-Pad35)") (class "Default")
      (node (ref "LCD") (pin "35") (pinfunction "35_35") (pintype "unspecified"))
    )
    (net (code "172") (name "unconnected-(LCD-Pad37)") (class "Default")
      (node (ref "LCD") (pin "37") (pinfunction "37_37") (pintype "unspecified"))
    )
    (net (code "173") (name "unconnected-(LCD-Pad38)") (class "Default")
      (node (ref "LCD") (pin "38") (pinfunction "38_38") (pintype "unspecified"))
    )
    (net (code "174") (name "unconnected-(LCD-Pad39)") (class "Default")
      (node (ref "LCD") (pin "39") (pinfunction "39_39") (pintype "unspecified"))
    )
    (net (code "175") (name "unconnected-(LCD-Pad40)") (class "Default")
      (node (ref "LCD") (pin "40") (pinfunction "40_40") (pintype "unspecified"))
    )
    (net (code "176") (name "unconnected-(RST-Pad1)") (class "Default")
      (node (ref "RST") (pin "1") (pinfunction "1_1") (pintype "unspecified+no_connect"))
    )
    (net (code "177") (name "unconnected-(RST-Pad2)") (class "Default")
      (node (ref "RST") (pin "2") (pinfunction "2_2") (pintype "unspecified+no_connect"))
    )
    (net (code "178") (name "unconnected-(RST-Pad3)") (class "Default")
      (node (ref "RST") (pin "3") (pinfunction "3_3") (pintype "unspecified+no_connect"))
    )
    (net (code "179") (name "unconnected-(RST-Pad6)") (class "Default")
      (node (ref "RST") (pin "6") (pinfunction "6_6") (pintype "unspecified+no_connect"))
    )
    (net (code "180") (name "unconnected-(U1-NC-PadF13)") (class "Default")
      (node (ref "U1") (pin "F13") (pinfunction "NC_F13") (pintype "unspecified+no_connect"))
    )
    (net (code "181") (name "unconnected-(U1-NC-PadL4)") (class "Default")
      (node (ref "U1") (pin "L4") (pinfunction "NC_L4") (pintype "unspecified+no_connect"))
    )
    (net (code "182") (name "unconnected-(U1-NC-PadM10)") (class "Default")
      (node (ref "U1") (pin "M10") (pinfunction "NC_M10") (pintype "unspecified+no_connect"))
    )
    (net (code "183") (name "unconnected-(U2-NC-PadE3)") (class "Default")
      (node (ref "U2") (pin "E3") (pinfunction "NC_E3") (pintype "input+no_connect"))
    )
    (net (code "184") (name "unconnected-(U2-NC-PadE7)") (class "Default")
      (node (ref "U2") (pin "E7") (pinfunction "NC_E7") (pintype "input+no_connect"))
    )
    (net (code "185") (name "unconnected-(U2-NC-PadH3)") (class "Default")
      (node (ref "U2") (pin "H3") (pinfunction "NC_H3") (pintype "input+no_connect"))
    )
    (net (code "186") (name "unconnected-(U2-NC-PadH7)") (class "Default")
      (node (ref "U2") (pin "H7") (pinfunction "NC_H7") (pintype "input+no_connect"))
    )
    (net (code "187") (name "unconnected-(U2-NC-PadK2)") (class "Default")
      (node (ref "U2") (pin "K2") (pinfunction "NC_K2") (pintype "input+no_connect"))
    )
    (net (code "188") (name "unconnected-(U2-NC-PadK3)") (class "Default")
      (node (ref "U2") (pin "K3") (pinfunction "NC_K3") (pintype "input+no_connect"))
    )
    (net (code "189") (name "unconnected-(U4-CTS#-Pad5)") (class "Default")
      (node (ref "U4") (pin "5") (pinfunction "CTS#_5") (pintype "unspecified+no_connect"))
    )
    (net (code "190") (name "unconnected-(U4-RTS#-Pad4)") (class "Default")
      (node (ref "U4") (pin "4") (pinfunction "RTS#_4") (pintype "unspecified+no_connect"))
    )
    (net (code "191") (name "unconnected-(U4-TNOW-Pad6)") (class "Default")
      (node (ref "U4") (pin "6") (pinfunction "TNOW_6") (pintype "unspecified+no_connect"))
    )
    (net (code "192") (name "unconnected-(USB_HS-SBU1-Pad9)") (class "Default")
      (node (ref "USB_HS") (pin "9") (pinfunction "SBU1_9") (pintype "unspecified+no_connect"))
    )
    (net (code "193") (name "unconnected-(USB_HS-SBU2-Pad3)") (class "Default")
      (node (ref "USB_HS") (pin "3") (pinfunction "SBU2_3") (pintype "unspecified+no_connect"))
    )
    (net (code "194") (name "unconnected-(USB_UART-SBU1-Pad9)") (class "Default")
      (node (ref "USB_UART") (pin "9") (pinfunction "SBU1_9") (pintype "unspecified+no_connect"))
    )
    (net (code "195") (name "unconnected-(USB_UART-SBU2-Pad3)") (class "Default")
      (node (ref "USB_UART") (pin "3") (pinfunction "SBU2_3") (pintype "unspecified+no_connect"))
    )
  )
)
